# EasyBMS.net
KiCad netlist of a schematic drawn in EAGLE
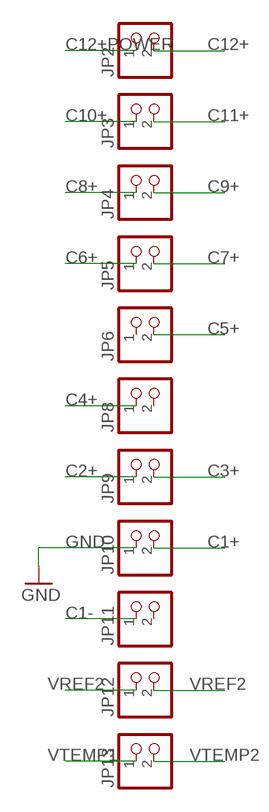
[diagram p0: schematic, sheet 1, part 1 of 3]
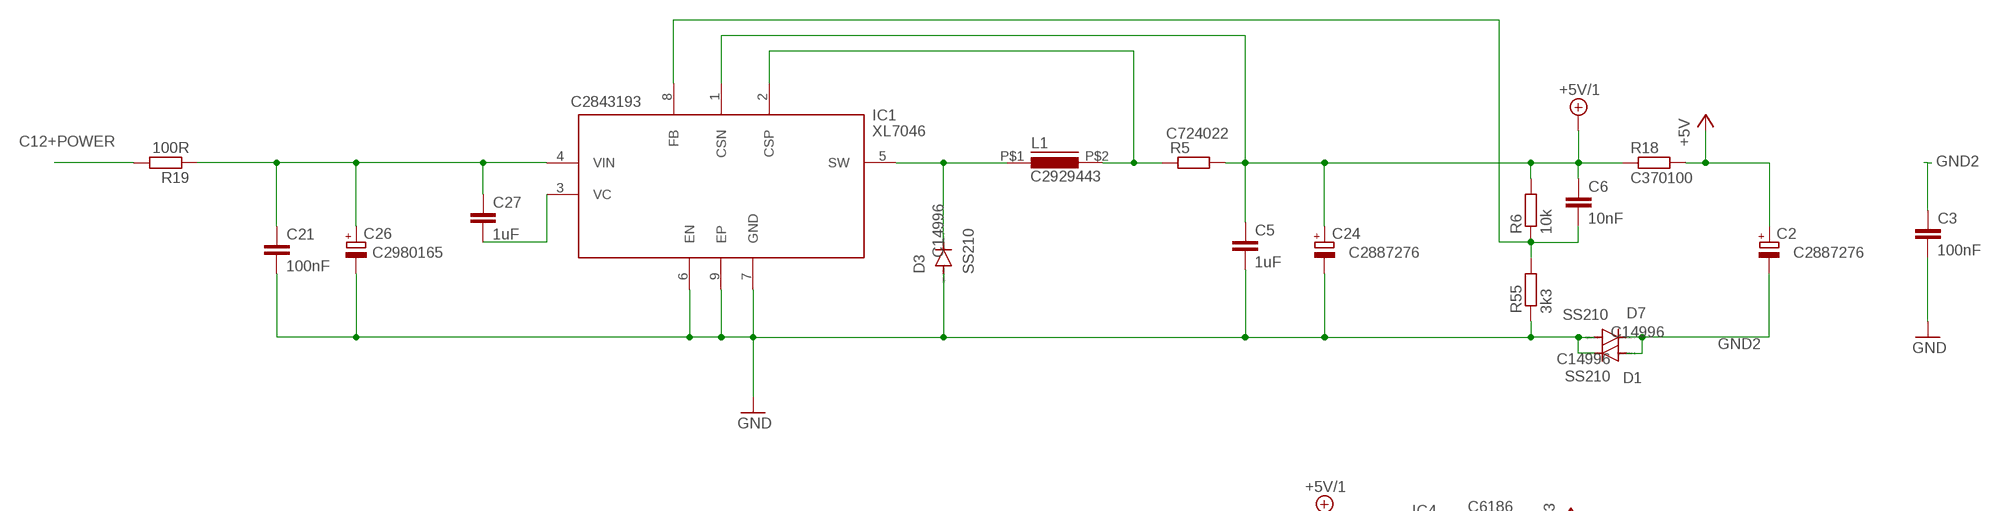
[diagram p1: schematic, sheet 1, part 2 of 3]
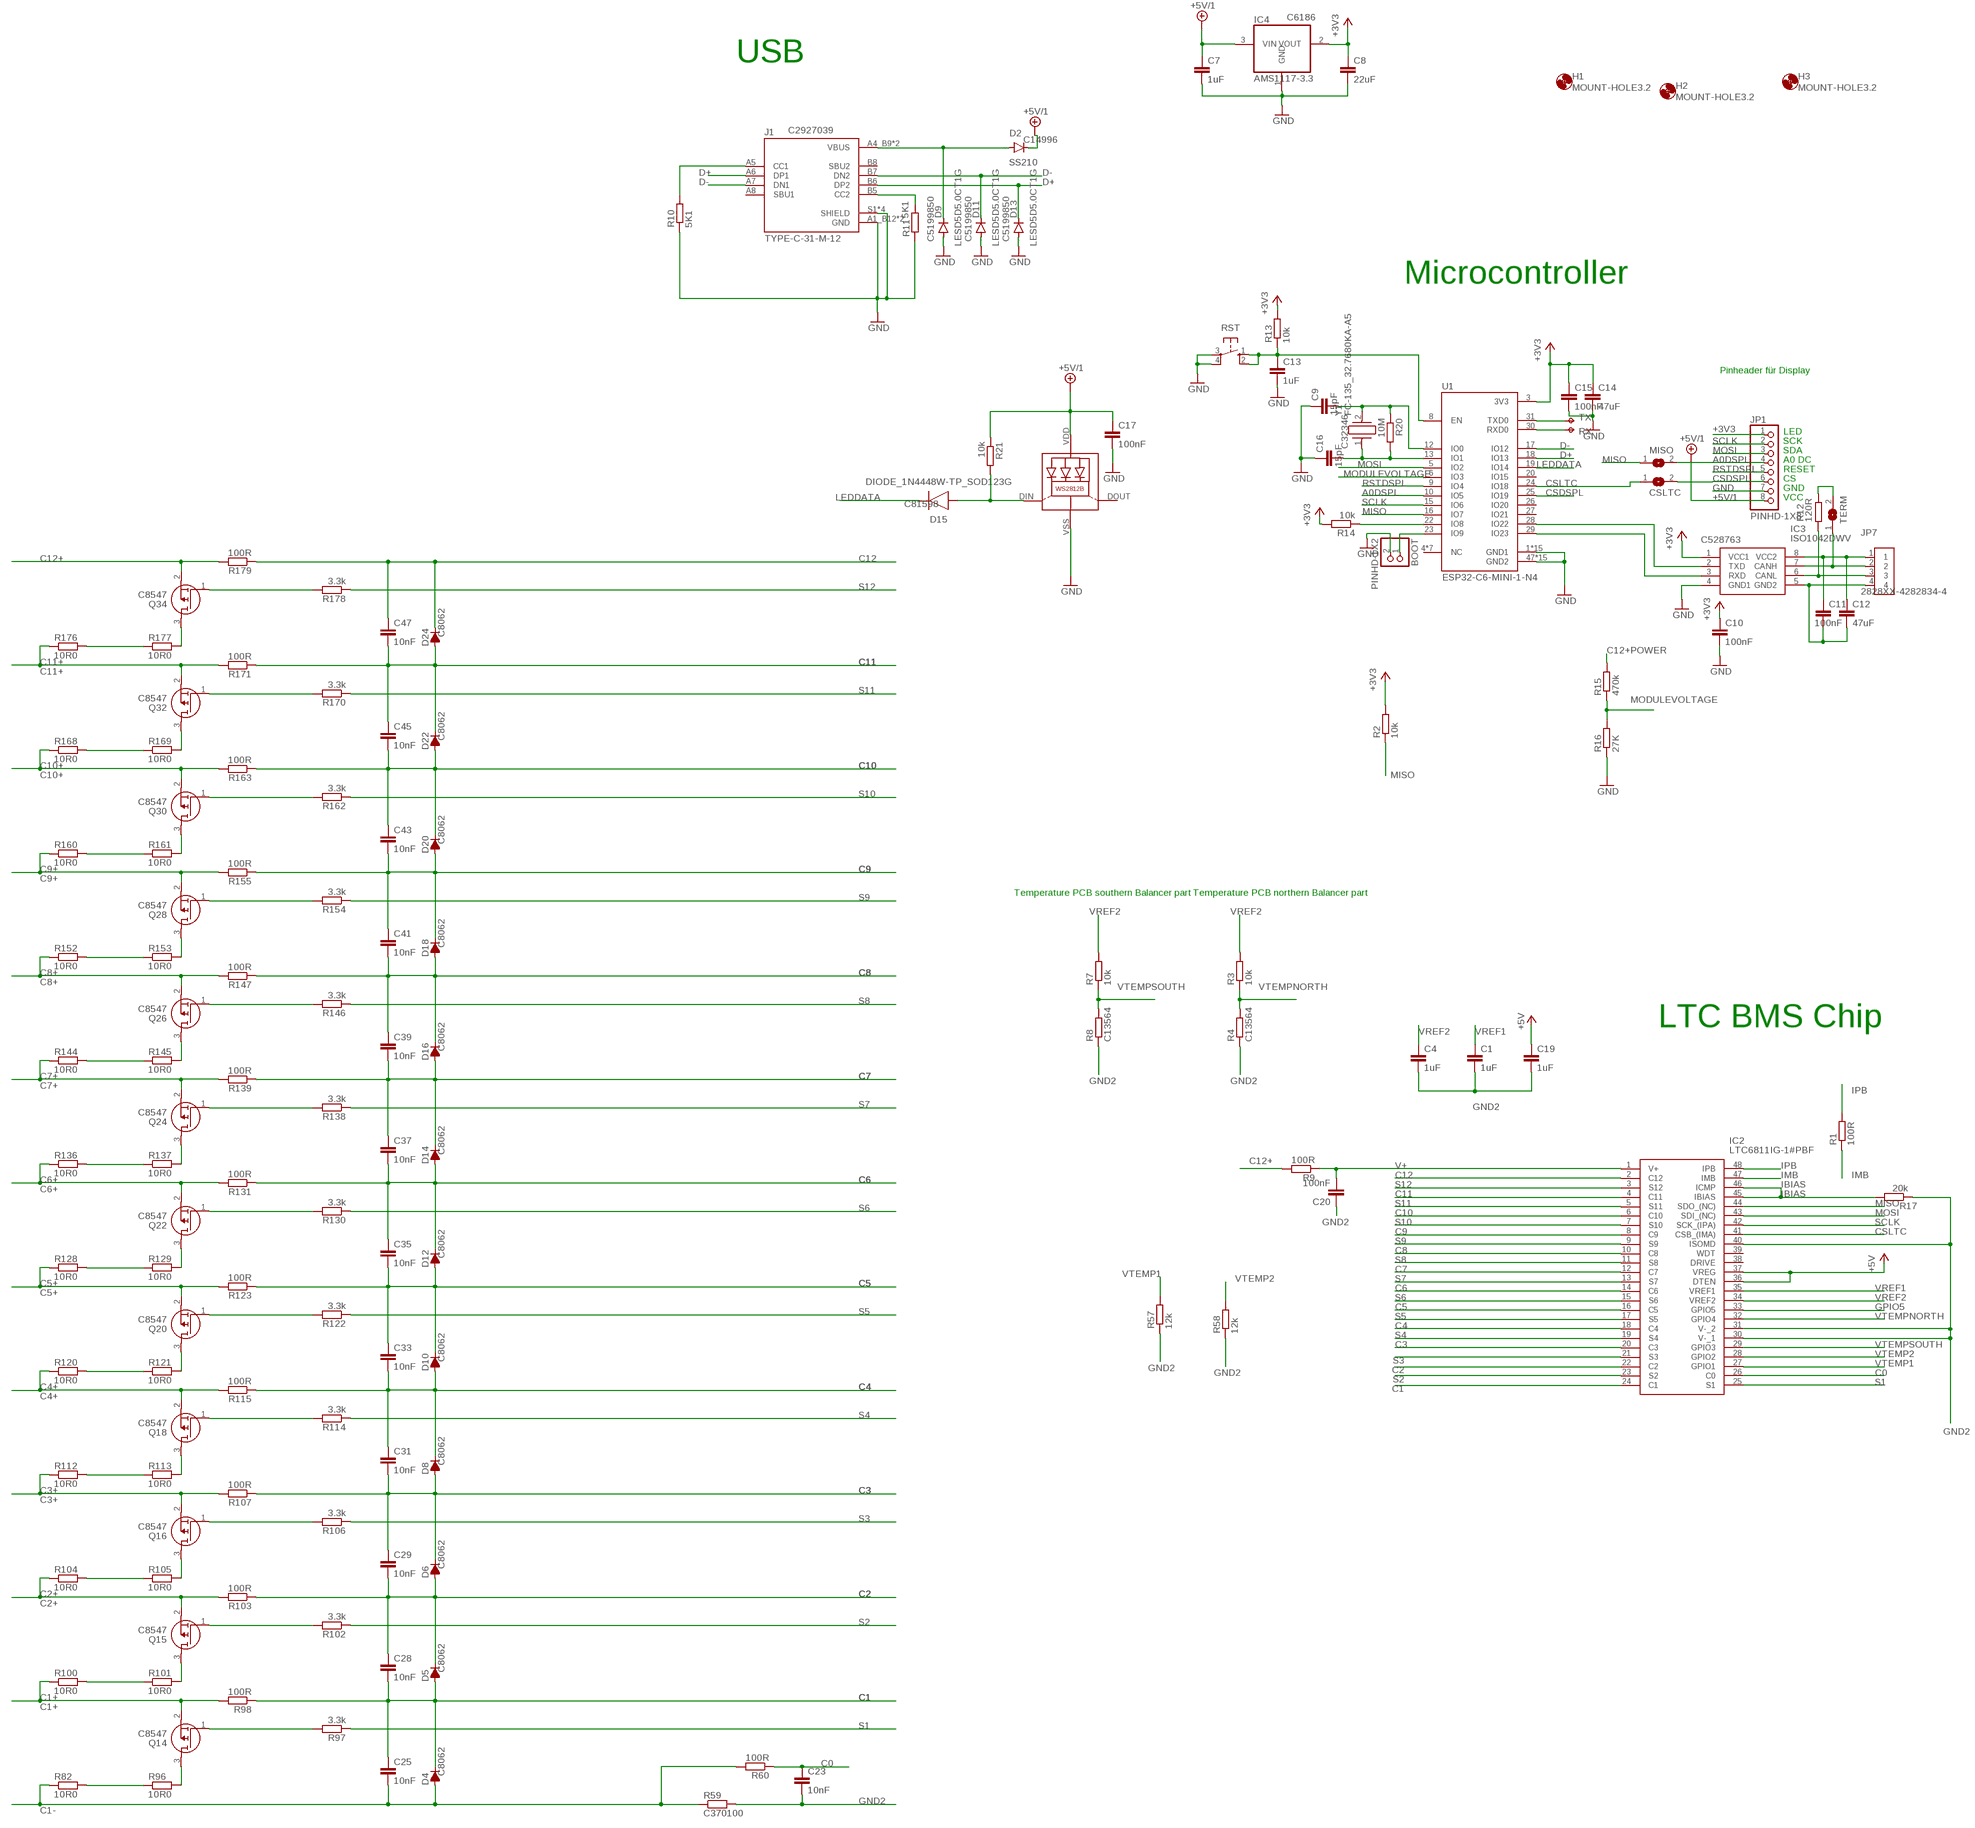
[diagram p2: schematic, sheet 1, part 3 of 3]

(export (version "E")
  (design (tool "Eeschema 10.0.6"))
  (components
    (comp (ref "BOOT")
      (value "PINHD-1X2")
      (footprint "eagle-import:1X02")
      (libsource (lib "eagle-import") (part "PINHD-1X2"))
    )
    (comp (ref "C1")
      (value "1uF")
      (footprint "eagle-import:C0402")
      (libsource (lib "eagle-import") (part "C-EUC0402"))
    )
    (comp (ref "C2")
      (value "CPOL-EU153CLV-0605")
      (footprint "eagle-import:153CLV-0605")
      (fields (field (name "LCSC") "C2887276"))
      (libsource (lib "eagle-import") (part "CPOL-EU153CLV-0605"))
    )
    (comp (ref "C3")
      (value "100nF")
      (footprint "eagle-import:C0402")
      (libsource (lib "eagle-import") (part "C-EUC0402"))
    )
    (comp (ref "C4")
      (value "1uF")
      (footprint "eagle-import:C0402")
      (libsource (lib "eagle-import") (part "C-EUC0402"))
    )
    (comp (ref "C5")
      (value "1uF")
      (footprint "eagle-import:C0402")
      (libsource (lib "eagle-import") (part "C-EUC0402"))
    )
    (comp (ref "C6")
      (value "10nF")
      (footprint "eagle-import:C0402")
      (libsource (lib "eagle-import") (part "C-EUC0402"))
    )
    (comp (ref "C7")
      (value "1uF")
      (footprint "eagle-import:C0402")
      (libsource (lib "eagle-import") (part "C-EUC0402"))
    )
    (comp (ref "C8")
      (value "22uF")
      (footprint "eagle-import:C0603")
      (libsource (lib "eagle-import") (part "C-EUC0603"))
    )
    (comp (ref "C9")
      (value "15pF")
      (footprint "eagle-import:C0402")
      (libsource (lib "eagle-import") (part "C-EUC0402"))
    )
    (comp (ref "C10")
      (value "100nF")
      (footprint "eagle-import:C0402")
      (libsource (lib "eagle-import") (part "C-EUC0402"))
    )
    (comp (ref "C11")
      (value "100nF")
      (footprint "eagle-import:C0402")
      (libsource (lib "eagle-import") (part "C-EUC0402"))
    )
    (comp (ref "C12")
      (value "47uF")
      (footprint "eagle-import:C1206")
      (libsource (lib "eagle-import") (part "C-EUC1206"))
    )
    (comp (ref "C13")
      (value "1uF")
      (footprint "eagle-import:C0402")
      (libsource (lib "eagle-import") (part "C-EUC0402"))
    )
    (comp (ref "C14")
      (value "47uF")
      (footprint "eagle-import:C0805")
      (libsource (lib "eagle-import") (part "C-EUC0805"))
    )
    (comp (ref "C15")
      (value "100nF")
      (footprint "eagle-import:C0402")
      (libsource (lib "eagle-import") (part "C-EUC0402"))
    )
    (comp (ref "C16")
      (value "15pF")
      (footprint "eagle-import:C0402")
      (libsource (lib "eagle-import") (part "C-EUC0402"))
    )
    (comp (ref "C17")
      (value "100nF")
      (footprint "eagle-import:C0402")
      (libsource (lib "eagle-import") (part "C-EUC0402"))
    )
    (comp (ref "C19")
      (value "1uF")
      (footprint "eagle-import:C0402")
      (libsource (lib "eagle-import") (part "C-EUC0402"))
    )
    (comp (ref "C20")
      (value "100nF")
      (footprint "eagle-import:C0805")
      (libsource (lib "eagle-import") (part "C-EUC0805"))
    )
    (comp (ref "C21")
      (value "100nF")
      (footprint "eagle-import:C0805")
      (libsource (lib "eagle-import") (part "C-EUC0805"))
    )
    (comp (ref "C23")
      (value "10nF")
      (footprint "eagle-import:C0402")
      (libsource (lib "eagle-import") (part "C-EUC0402"))
    )
    (comp (ref "C24")
      (value "CPOL-EU153CLV-0605")
      (footprint "eagle-import:153CLV-0605")
      (fields (field (name "LCSC") "C2887276"))
      (libsource (lib "eagle-import") (part "CPOL-EU153CLV-0605"))
    )
    (comp (ref "C25")
      (value "10nF")
      (footprint "eagle-import:C0402")
      (libsource (lib "eagle-import") (part "C-EUC0402"))
    )
    (comp (ref "C26")
      (value "CPOL-EU153CLV-0605")
      (footprint "eagle-import:153CLV-0605")
      (fields (field (name "LCSC") "C2980165"))
      (libsource (lib "eagle-import") (part "CPOL-EU153CLV-0605"))
    )
    (comp (ref "C27")
      (value "1uF")
      (footprint "eagle-import:C0603")
      (libsource (lib "eagle-import") (part "C-EUC0603"))
    )
    (comp (ref "C28")
      (value "10nF")
      (footprint "eagle-import:C0402")
      (libsource (lib "eagle-import") (part "C-EUC0402"))
    )
    (comp (ref "C29")
      (value "10nF")
      (footprint "eagle-import:C0402")
      (libsource (lib "eagle-import") (part "C-EUC0402"))
    )
    (comp (ref "C31")
      (value "10nF")
      (footprint "eagle-import:C0402")
      (libsource (lib "eagle-import") (part "C-EUC0402"))
    )
    (comp (ref "C33")
      (value "10nF")
      (footprint "eagle-import:C0402")
      (libsource (lib "eagle-import") (part "C-EUC0402"))
    )
    (comp (ref "C35")
      (value "10nF")
      (footprint "eagle-import:C0402")
      (libsource (lib "eagle-import") (part "C-EUC0402"))
    )
    (comp (ref "C37")
      (value "10nF")
      (footprint "eagle-import:C0402")
      (libsource (lib "eagle-import") (part "C-EUC0402"))
    )
    (comp (ref "C39")
      (value "10nF")
      (footprint "eagle-import:C0402")
      (libsource (lib "eagle-import") (part "C-EUC0402"))
    )
    (comp (ref "C41")
      (value "10nF")
      (footprint "eagle-import:C0402")
      (libsource (lib "eagle-import") (part "C-EUC0402"))
    )
    (comp (ref "C43")
      (value "10nF")
      (footprint "eagle-import:C0402")
      (libsource (lib "eagle-import") (part "C-EUC0402"))
    )
    (comp (ref "C45")
      (value "10nF")
      (footprint "eagle-import:C0402")
      (libsource (lib "eagle-import") (part "C-EUC0402"))
    )
    (comp (ref "C47")
      (value "10nF")
      (footprint "eagle-import:C0402")
      (libsource (lib "eagle-import") (part "C-EUC0402"))
    )
    (comp (ref "CSLTC")
      (value "SJ")
      (footprint "eagle-import:SJ")
      (libsource (lib "eagle-import") (part "SJ"))
    )
    (comp (ref "D1")
      (value "SS210")
      (footprint "eagle-import:DO214AC")
      (fields (field (name "LCSC") "C14996"))
      (libsource (lib "eagle-import") (part "DIODE-DO214AC"))
    )
    (comp (ref "D2")
      (value "SS210")
      (footprint "eagle-import:DO214AC")
      (fields (field (name "LCSC") "C14996"))
      (libsource (lib "eagle-import") (part "DIODE-DO214AC"))
    )
    (comp (ref "D3")
      (value "SS210")
      (footprint "eagle-import:DO214AC")
      (fields (field (name "LCSC") "C14996"))
      (libsource (lib "eagle-import") (part "DIODE-DO214AC"))
    )
    (comp (ref "D4")
      (value "D-FILL-MLL-34")
      (footprint "eagle-import:MELF-MLL34")
      (fields (field (name "LCSC") "C8062"))
      (libsource (lib "eagle-import") (part "D-FILL-MLL-34"))
    )
    (comp (ref "D5")
      (value "D-FILL-MLL-34")
      (footprint "eagle-import:MELF-MLL34")
      (fields (field (name "LCSC") "C8062"))
      (libsource (lib "eagle-import") (part "D-FILL-MLL-34"))
    )
    (comp (ref "D6")
      (value "D-FILL-MLL-34")
      (footprint "eagle-import:MELF-MLL34")
      (fields (field (name "LCSC") "C8062"))
      (libsource (lib "eagle-import") (part "D-FILL-MLL-34"))
    )
    (comp (ref "D7")
      (value "SS210")
      (footprint "eagle-import:DO214AC")
      (fields (field (name "LCSC") "C14996"))
      (libsource (lib "eagle-import") (part "DIODE-DO214AC"))
    )
    (comp (ref "D8")
      (value "D-FILL-MLL-34")
      (footprint "eagle-import:MELF-MLL34")
      (fields (field (name "LCSC") "C8062"))
      (libsource (lib "eagle-import") (part "D-FILL-MLL-34"))
    )
    (comp (ref "D9")
      (value "LESD5D5.0CT1G")
      (footprint "eagle-import:SOD523")
      (fields (field (name "LCSC") "C5199850"))
      (libsource (lib "eagle-import") (part "DIODE-SOD523"))
    )
    (comp (ref "D10")
      (value "D-FILL-MLL-34")
      (footprint "eagle-import:MELF-MLL34")
      (fields (field (name "LCSC") "C8062"))
      (libsource (lib "eagle-import") (part "D-FILL-MLL-34"))
    )
    (comp (ref "D11")
      (value "LESD5D5.0CT1G")
      (footprint "eagle-import:SOD523")
      (fields (field (name "LCSC") "C5199850"))
      (libsource (lib "eagle-import") (part "DIODE-SOD523"))
    )
    (comp (ref "D12")
      (value "D-FILL-MLL-34")
      (footprint "eagle-import:MELF-MLL34")
      (fields (field (name "LCSC") "C8062"))
      (libsource (lib "eagle-import") (part "D-FILL-MLL-34"))
    )
    (comp (ref "D13")
      (value "LESD5D5.0CT1G")
      (footprint "eagle-import:SOD523")
      (fields (field (name "LCSC") "C5199850"))
      (libsource (lib "eagle-import") (part "DIODE-SOD523"))
    )
    (comp (ref "D14")
      (value "D-FILL-MLL-34")
      (footprint "eagle-import:MELF-MLL34")
      (fields (field (name "LCSC") "C8062"))
      (libsource (lib "eagle-import") (part "D-FILL-MLL-34"))
    )
    (comp (ref "D15")
      (value "DIODE_1N4448W-TP_SOD123G")
      (footprint "eagle-import:SOD3715X135")
      (fields
        (field (name "MANUFACTURER") "Micro Commercial Co")
        (field (name "MPN") "1N4448W-TP")
        (field (name "LCSC") "C81598")
      )
      (libsource (lib "eagle-import") (part "DIODE__SOD123G1N4448W-TP"))
    )
    (comp (ref "D16")
      (value "D-FILL-MLL-34")
      (footprint "eagle-import:MELF-MLL34")
      (fields (field (name "LCSC") "C8062"))
      (libsource (lib "eagle-import") (part "D-FILL-MLL-34"))
    )
    (comp (ref "D18")
      (value "D-FILL-MLL-34")
      (footprint "eagle-import:MELF-MLL34")
      (fields (field (name "LCSC") "C8062"))
      (libsource (lib "eagle-import") (part "D-FILL-MLL-34"))
    )
    (comp (ref "D20")
      (value "D-FILL-MLL-34")
      (footprint "eagle-import:MELF-MLL34")
      (fields (field (name "LCSC") "C8062"))
      (libsource (lib "eagle-import") (part "D-FILL-MLL-34"))
    )
    (comp (ref "D22")
      (value "D-FILL-MLL-34")
      (footprint "eagle-import:MELF-MLL34")
      (fields (field (name "LCSC") "C8062"))
      (libsource (lib "eagle-import") (part "D-FILL-MLL-34"))
    )
    (comp (ref "D24")
      (value "D-FILL-MLL-34")
      (footprint "eagle-import:MELF-MLL34")
      (fields (field (name "LCSC") "C8062"))
      (libsource (lib "eagle-import") (part "D-FILL-MLL-34"))
    )
    (comp (ref "H1")
      (value "MOUNT-HOLE3.2")
      (footprint "eagle-import:3,2")
      (libsource (lib "eagle-import") (part "MOUNT-HOLE3.2"))
    )
    (comp (ref "H2")
      (value "MOUNT-HOLE3.2")
      (footprint "eagle-import:3,2")
      (libsource (lib "eagle-import") (part "MOUNT-HOLE3.2"))
    )
    (comp (ref "H3")
      (value "MOUNT-HOLE3.2")
      (footprint "eagle-import:3,2")
      (libsource (lib "eagle-import") (part "MOUNT-HOLE3.2"))
    )
    (comp (ref "IC1")
      (value "XL7046")
      (footprint "eagle-import:SOIC127P600X170-9N")
      (fields
        (field (name "MANUFACTURER_PART_NUMBER") "DRV103H")
        (field (name "MOUSER_PART_NUMBER") "595-DRV103H")
        (field (name "LCSC") "C2843193")
      )
      (libsource (lib "eagle-import") (part "XL7046"))
    )
    (comp (ref "IC2")
      (value "LTC6811IG-1#PBF")
      (footprint "eagle-import:SOP50P780X200-48N")
      (fields (field (name "MOUSER_PART_NUMBER") "584-LTC6811IG-1#PBF"))
      (libsource (lib "eagle-import") (part "LTC6811IG-1#PBF"))
    )
    (comp (ref "IC3")
      (value "ISO1042DWV")
      (footprint "eagle-import:SOIC127P1150X280-8N")
      (fields (field (name "MOUSER_PART_NUMBER") "595-ISO1042DWV") (field (name "LCSC") "C528763"))
      (libsource (lib "eagle-import") (part "ISO1042DWV"))
    )
    (comp (ref "IC4")
      (value "AMS1117-3.3")
      (footprint "eagle-import:SOT223")
      (fields (field (name "MPN") "REG1117") (field (name "LCSC") "C6186"))
      (libsource (lib "eagle-import") (part "REG1117"))
    )
    (comp (ref "J1")
      (value "TYPE-C-31-M-12")
      (footprint "eagle-import:HRO_TYPE-C-31-M-12")
      (fields (field (name "MF") "HRO Electronics Co., Ltd.") (field (name "LCSC") "C2927039"))
      (libsource (lib "eagle-import") (part "TYPE-C-31-M-12"))
    )
    (comp (ref "JP1")
      (value "PINHD-1X8")
      (footprint "eagle-import:1X08")
      (libsource (lib "eagle-import") (part "PINHD-1X8"))
    )
    (comp (ref "JP2")
      (value "PINHD-1X2")
      (footprint "eagle-import:1X02")
      (libsource (lib "eagle-import") (part "pinhead_own_PINHD-1X2"))
    )
    (comp (ref "JP3")
      (value "PINHD-1X2")
      (footprint "eagle-import:1X02")
      (libsource (lib "eagle-import") (part "pinhead_own_PINHD-1X2"))
    )
    (comp (ref "JP4")
      (value "PINHD-1X2")
      (footprint "eagle-import:1X02")
      (libsource (lib "eagle-import") (part "pinhead_own_PINHD-1X2"))
    )
    (comp (ref "JP5")
      (value "PINHD-1X2")
      (footprint "eagle-import:1X02")
      (libsource (lib "eagle-import") (part "pinhead_own_PINHD-1X2"))
    )
    (comp (ref "JP6")
      (value "PINHD-1X2")
      (footprint "eagle-import:1X02")
      (libsource (lib "eagle-import") (part "pinhead_own_PINHD-1X2"))
    )
    (comp (ref "JP7")
      (value "2828XX-4282834-4")
      (footprint "eagle-import:TERMBLK_254-4N")
      (fields (field (name "MANUFACTURER") "TE Connectivity AMP Connectors") (field (name "MPN") "282834-4"))
      (libsource (lib "eagle-import") (part "2828XX-4282834-4"))
    )
    (comp (ref "JP8")
      (value "PINHD-1X2")
      (footprint "eagle-import:1X02")
      (libsource (lib "eagle-import") (part "pinhead_own_PINHD-1X2"))
    )
    (comp (ref "JP9")
      (value "PINHD-1X2")
      (footprint "eagle-import:1X02")
      (libsource (lib "eagle-import") (part "pinhead_own_PINHD-1X2"))
    )
    (comp (ref "JP10")
      (value "PINHD-1X2")
      (footprint "eagle-import:1X02")
      (libsource (lib "eagle-import") (part "pinhead_own_PINHD-1X2"))
    )
    (comp (ref "JP11")
      (value "PINHD-1X2")
      (footprint "eagle-import:1X02")
      (libsource (lib "eagle-import") (part "pinhead_own_PINHD-1X2"))
    )
    (comp (ref "JP12")
      (value "PINHD-1X2")
      (footprint "eagle-import:1X02")
      (libsource (lib "eagle-import") (part "pinhead_own_PINHD-1X2"))
    )
    (comp (ref "JP13")
      (value "PINHD-1X2")
      (footprint "eagle-import:1X02")
      (libsource (lib "eagle-import") (part "pinhead_own_PINHD-1X2"))
    )
    (comp (ref "L1")
      (value "C2929443")
      (footprint "eagle-import:CY75-100UH")
      (libsource (lib "eagle-import") (part "CY75-100UH"))
    )
    (comp (ref "LED2")
      (value "XL-1615RGBC-WS2812B")
      (footprint "eagle-import:XL-1615RGBC-WS2812B")
      (libsource (lib "eagle-import") (part "XL-1615RGBC-WS2812B"))
    )
    (comp (ref "MISO")
      (value "SJ")
      (footprint "eagle-import:SJ")
      (libsource (lib "eagle-import") (part "SJ"))
    )
    (comp (ref "Q14")
      (value "C8547")
      (footprint "eagle-import:PG-SOT-23")
      (fields
        (field (name "MANUFACTURER_PART_NUMBER") "BSS308PEH6327XTSA1")
        (field (name "MOUSER_PART_NUMBER") "726-BSS308PEH6327XTS")
      )
      (libsource (lib "eagle-import") (part "BSS308PEH6327XTSA1"))
    )
    (comp (ref "Q15")
      (value "C8547")
      (footprint "eagle-import:PG-SOT-23")
      (fields
        (field (name "MANUFACTURER_PART_NUMBER") "BSS308PEH6327XTSA1")
        (field (name "MOUSER_PART_NUMBER") "726-BSS308PEH6327XTS")
      )
      (libsource (lib "eagle-import") (part "BSS308PEH6327XTSA1"))
    )
    (comp (ref "Q16")
      (value "C8547")
      (footprint "eagle-import:PG-SOT-23")
      (fields
        (field (name "MANUFACTURER_PART_NUMBER") "BSS308PEH6327XTSA1")
        (field (name "MOUSER_PART_NUMBER") "726-BSS308PEH6327XTS")
      )
      (libsource (lib "eagle-import") (part "BSS308PEH6327XTSA1"))
    )
    (comp (ref "Q18")
      (value "C8547")
      (footprint "eagle-import:PG-SOT-23")
      (fields
        (field (name "MANUFACTURER_PART_NUMBER") "BSS308PEH6327XTSA1")
        (field (name "MOUSER_PART_NUMBER") "726-BSS308PEH6327XTS")
      )
      (libsource (lib "eagle-import") (part "BSS308PEH6327XTSA1"))
    )
    (comp (ref "Q20")
      (value "C8547")
      (footprint "eagle-import:PG-SOT-23")
      (fields
        (field (name "MANUFACTURER_PART_NUMBER") "BSS308PEH6327XTSA1")
        (field (name "MOUSER_PART_NUMBER") "726-BSS308PEH6327XTS")
      )
      (libsource (lib "eagle-import") (part "BSS308PEH6327XTSA1"))
    )
    (comp (ref "Q22")
      (value "C8547")
      (footprint "eagle-import:PG-SOT-23")
      (fields
        (field (name "MANUFACTURER_PART_NUMBER") "BSS308PEH6327XTSA1")
        (field (name "MOUSER_PART_NUMBER") "726-BSS308PEH6327XTS")
      )
      (libsource (lib "eagle-import") (part "BSS308PEH6327XTSA1"))
    )
    (comp (ref "Q24")
      (value "C8547")
      (footprint "eagle-import:PG-SOT-23")
      (fields
        (field (name "MANUFACTURER_PART_NUMBER") "BSS308PEH6327XTSA1")
        (field (name "MOUSER_PART_NUMBER") "726-BSS308PEH6327XTS")
      )
      (libsource (lib "eagle-import") (part "BSS308PEH6327XTSA1"))
    )
    (comp (ref "Q26")
      (value "C8547")
      (footprint "eagle-import:PG-SOT-23")
      (fields
        (field (name "MANUFACTURER_PART_NUMBER") "BSS308PEH6327XTSA1")
        (field (name "MOUSER_PART_NUMBER") "726-BSS308PEH6327XTS")
      )
      (libsource (lib "eagle-import") (part "BSS308PEH6327XTSA1"))
    )
    (comp (ref "Q28")
      (value "C8547")
      (footprint "eagle-import:PG-SOT-23")
      (fields
        (field (name "MANUFACTURER_PART_NUMBER") "BSS308PEH6327XTSA1")
        (field (name "MOUSER_PART_NUMBER") "726-BSS308PEH6327XTS")
      )
      (libsource (lib "eagle-import") (part "BSS308PEH6327XTSA1"))
    )
    (comp (ref "Q30")
      (value "C8547")
      (footprint "eagle-import:PG-SOT-23")
      (fields
        (field (name "MANUFACTURER_PART_NUMBER") "BSS308PEH6327XTSA1")
        (field (name "MOUSER_PART_NUMBER") "726-BSS308PEH6327XTS")
      )
      (libsource (lib "eagle-import") (part "BSS308PEH6327XTSA1"))
    )
    (comp (ref "Q32")
      (value "C8547")
      (footprint "eagle-import:PG-SOT-23")
      (fields
        (field (name "MANUFACTURER_PART_NUMBER") "BSS308PEH6327XTSA1")
        (field (name "MOUSER_PART_NUMBER") "726-BSS308PEH6327XTS")
      )
      (libsource (lib "eagle-import") (part "BSS308PEH6327XTSA1"))
    )
    (comp (ref "Q34")
      (value "C8547")
      (footprint "eagle-import:PG-SOT-23")
      (fields
        (field (name "MANUFACTURER_PART_NUMBER") "BSS308PEH6327XTSA1")
        (field (name "MOUSER_PART_NUMBER") "726-BSS308PEH6327XTS")
      )
      (libsource (lib "eagle-import") (part "BSS308PEH6327XTSA1"))
    )
    (comp (ref "R1")
      (value "100R")
      (footprint "eagle-import:R0603")
      (libsource (lib "eagle-import") (part "R-EU_R0603"))
    )
    (comp (ref "R2")
      (value "10k")
      (footprint "eagle-import:R0402")
      (libsource (lib "eagle-import") (part "R-EU_R0402"))
    )
    (comp (ref "R3")
      (value "10k")
      (footprint "eagle-import:R0603")
      (libsource (lib "eagle-import") (part "R-EU_R0603"))
    )
    (comp (ref "R4")
      (value "C13564")
      (footprint "eagle-import:R0603")
      (libsource (lib "eagle-import") (part "R-EU_R0603"))
    )
    (comp (ref "R5")
      (value "R-EU_R0402")
      (footprint "eagle-import:R0402")
      (fields (field (name "LCSC") "C724022"))
      (libsource (lib "eagle-import") (part "R-EU_R0402"))
    )
    (comp (ref "R6")
      (value "10k")
      (footprint "eagle-import:R0402")
      (libsource (lib "eagle-import") (part "R-EU_R0402"))
    )
    (comp (ref "R7")
      (value "10k")
      (footprint "eagle-import:R0603")
      (libsource (lib "eagle-import") (part "R-EU_R0603"))
    )
    (comp (ref "R8")
      (value "C13564")
      (footprint "eagle-import:R0603")
      (libsource (lib "eagle-import") (part "R-EU_R0603"))
    )
    (comp (ref "R9")
      (value "100R")
      (footprint "eagle-import:R0402")
      (libsource (lib "eagle-import") (part "R-EU_R0402"))
    )
    (comp (ref "R10")
      (value "5K1")
      (footprint "eagle-import:R0402")
      (libsource (lib "eagle-import") (part "R-EU_R0402"))
    )
    (comp (ref "R11")
      (value "5K1")
      (footprint "eagle-import:R0402")
      (libsource (lib "eagle-import") (part "R-EU_R0402"))
    )
    (comp (ref "R12")
      (value "120R")
      (footprint "eagle-import:R0402")
      (libsource (lib "eagle-import") (part "R-EU_R0402"))
    )
    (comp (ref "R13")
      (value "10k")
      (footprint "eagle-import:R0402")
      (libsource (lib "eagle-import") (part "R-EU_R0402"))
    )
    (comp (ref "R14")
      (value "10k")
      (footprint "eagle-import:R0402")
      (libsource (lib "eagle-import") (part "R-EU_R0402"))
    )
    (comp (ref "R15")
      (value "470k")
      (footprint "eagle-import:R0603")
      (libsource (lib "eagle-import") (part "R-EU_R0603"))
    )
    (comp (ref "R16")
      (value "27K")
      (footprint "eagle-import:R0603")
      (libsource (lib "eagle-import") (part "R-EU_R0603"))
    )
    (comp (ref "R17")
      (value "20k")
      (footprint "eagle-import:R0603")
      (libsource (lib "eagle-import") (part "R-EU_R0603"))
    )
    (comp (ref "R18")
      (value "C370100")
      (footprint "eagle-import:R1206")
      (libsource (lib "eagle-import") (part "R-EU_R1206"))
    )
    (comp (ref "R19")
      (value "100R")
      (footprint "eagle-import:R1206")
      (libsource (lib "eagle-import") (part "R-EU_R1206"))
    )
    (comp (ref "R20")
      (value "10M")
      (footprint "eagle-import:R0402")
      (libsource (lib "eagle-import") (part "R-EU_R0402"))
    )
    (comp (ref "R21")
      (value "10k")
      (footprint "eagle-import:R0402")
      (libsource (lib "eagle-import") (part "R-EU_R0402"))
    )
    (comp (ref "R55")
      (value "3k3")
      (footprint "eagle-import:R0402")
      (libsource (lib "eagle-import") (part "R-EU_R0402"))
    )
    (comp (ref "R57")
      (value "12k")
      (footprint "eagle-import:R0402")
      (libsource (lib "eagle-import") (part "R-EU_R0402"))
    )
    (comp (ref "R58")
      (value "12k")
      (footprint "eagle-import:R0402")
      (libsource (lib "eagle-import") (part "R-EU_R0402"))
    )
    (comp (ref "R59")
      (value "C370100")
      (footprint "eagle-import:R1206")
      (libsource (lib "eagle-import") (part "R-EU_R1206"))
    )
    (comp (ref "R60")
      (value "100R")
      (footprint "eagle-import:R0402")
      (libsource (lib "eagle-import") (part "R-EU_R0402"))
    )
    (comp (ref "R82")
      (value "10R0")
      (footprint "eagle-import:R1206")
      (libsource (lib "eagle-import") (part "R-EU_R1206"))
    )
    (comp (ref "R96")
      (value "10R0")
      (footprint "eagle-import:R1206")
      (libsource (lib "eagle-import") (part "R-EU_R1206"))
    )
    (comp (ref "R97")
      (value "3.3k")
      (footprint "eagle-import:R0402")
      (libsource (lib "eagle-import") (part "R-EU_R0402"))
    )
    (comp (ref "R98")
      (value "100R")
      (footprint "eagle-import:R0402")
      (libsource (lib "eagle-import") (part "R-EU_R0402"))
    )
    (comp (ref "R100")
      (value "10R0")
      (footprint "eagle-import:R1206")
      (libsource (lib "eagle-import") (part "R-EU_R1206"))
    )
    (comp (ref "R101")
      (value "10R0")
      (footprint "eagle-import:R1206")
      (libsource (lib "eagle-import") (part "R-EU_R1206"))
    )
    (comp (ref "R102")
      (value "3.3k")
      (footprint "eagle-import:R0402")
      (libsource (lib "eagle-import") (part "R-EU_R0402"))
    )
    (comp (ref "R103")
      (value "100R")
      (footprint "eagle-import:R0402")
      (libsource (lib "eagle-import") (part "R-EU_R0402"))
    )
    (comp (ref "R104")
      (value "10R0")
      (footprint "eagle-import:R1206")
      (libsource (lib "eagle-import") (part "R-EU_R1206"))
    )
    (comp (ref "R105")
      (value "10R0")
      (footprint "eagle-import:R1206")
      (libsource (lib "eagle-import") (part "R-EU_R1206"))
    )
    (comp (ref "R106")
      (value "3.3k")
      (footprint "eagle-import:R0402")
      (libsource (lib "eagle-import") (part "R-EU_R0402"))
    )
    (comp (ref "R107")
      (value "100R")
      (footprint "eagle-import:R0402")
      (libsource (lib "eagle-import") (part "R-EU_R0402"))
    )
    (comp (ref "R112")
      (value "10R0")
      (footprint "eagle-import:R1206")
      (libsource (lib "eagle-import") (part "R-EU_R1206"))
    )
    (comp (ref "R113")
      (value "10R0")
      (footprint "eagle-import:R1206")
      (libsource (lib "eagle-import") (part "R-EU_R1206"))
    )
    (comp (ref "R114")
      (value "3.3k")
      (footprint "eagle-import:R0402")
      (libsource (lib "eagle-import") (part "R-EU_R0402"))
    )
    (comp (ref "R115")
      (value "100R")
      (footprint "eagle-import:R0402")
      (libsource (lib "eagle-import") (part "R-EU_R0402"))
    )
    (comp (ref "R120")
      (value "10R0")
      (footprint "eagle-import:R1206")
      (libsource (lib "eagle-import") (part "R-EU_R1206"))
    )
    (comp (ref "R121")
      (value "10R0")
      (footprint "eagle-import:R1206")
      (libsource (lib "eagle-import") (part "R-EU_R1206"))
    )
    (comp (ref "R122")
      (value "3.3k")
      (footprint "eagle-import:R0402")
      (libsource (lib "eagle-import") (part "R-EU_R0402"))
    )
    (comp (ref "R123")
      (value "100R")
      (footprint "eagle-import:R0402")
      (libsource (lib "eagle-import") (part "R-EU_R0402"))
    )
    (comp (ref "R128")
      (value "10R0")
      (footprint "eagle-import:R1206")
      (libsource (lib "eagle-import") (part "R-EU_R1206"))
    )
    (comp (ref "R129")
      (value "10R0")
      (footprint "eagle-import:R1206")
      (libsource (lib "eagle-import") (part "R-EU_R1206"))
    )
    (comp (ref "R130")
      (value "3.3k")
      (footprint "eagle-import:R0402")
      (libsource (lib "eagle-import") (part "R-EU_R0402"))
    )
    (comp (ref "R131")
      (value "100R")
      (footprint "eagle-import:R0402")
      (libsource (lib "eagle-import") (part "R-EU_R0402"))
    )
    (comp (ref "R136")
      (value "10R0")
      (footprint "eagle-import:R1206")
      (libsource (lib "eagle-import") (part "R-EU_R1206"))
    )
    (comp (ref "R137")
      (value "10R0")
      (footprint "eagle-import:R1206")
      (libsource (lib "eagle-import") (part "R-EU_R1206"))
    )
    (comp (ref "R138")
      (value "3.3k")
      (footprint "eagle-import:R0402")
      (libsource (lib "eagle-import") (part "R-EU_R0402"))
    )
    (comp (ref "R139")
      (value "100R")
      (footprint "eagle-import:R0402")
      (libsource (lib "eagle-import") (part "R-EU_R0402"))
    )
    (comp (ref "R144")
      (value "10R0")
      (footprint "eagle-import:R1206")
      (libsource (lib "eagle-import") (part "R-EU_R1206"))
    )
    (comp (ref "R145")
      (value "10R0")
      (footprint "eagle-import:R1206")
      (libsource (lib "eagle-import") (part "R-EU_R1206"))
    )
    (comp (ref "R146")
      (value "3.3k")
      (footprint "eagle-import:R0402")
      (libsource (lib "eagle-import") (part "R-EU_R0402"))
    )
    (comp (ref "R147")
      (value "100R")
      (footprint "eagle-import:R0402")
      (libsource (lib "eagle-import") (part "R-EU_R0402"))
    )
    (comp (ref "R152")
      (value "10R0")
      (footprint "eagle-import:R1206")
      (libsource (lib "eagle-import") (part "R-EU_R1206"))
    )
    (comp (ref "R153")
      (value "10R0")
      (footprint "eagle-import:R1206")
      (libsource (lib "eagle-import") (part "R-EU_R1206"))
    )
    (comp (ref "R154")
      (value "3.3k")
      (footprint "eagle-import:R0402")
      (libsource (lib "eagle-import") (part "R-EU_R0402"))
    )
    (comp (ref "R155")
      (value "100R")
      (footprint "eagle-import:R0402")
      (libsource (lib "eagle-import") (part "R-EU_R0402"))
    )
    (comp (ref "R160")
      (value "10R0")
      (footprint "eagle-import:R1206")
      (libsource (lib "eagle-import") (part "R-EU_R1206"))
    )
    (comp (ref "R161")
      (value "10R0")
      (footprint "eagle-import:R1206")
      (libsource (lib "eagle-import") (part "R-EU_R1206"))
    )
    (comp (ref "R162")
      (value "3.3k")
      (footprint "eagle-import:R0402")
      (libsource (lib "eagle-import") (part "R-EU_R0402"))
    )
    (comp (ref "R163")
      (value "100R")
      (footprint "eagle-import:R0402")
      (libsource (lib "eagle-import") (part "R-EU_R0402"))
    )
    (comp (ref "R168")
      (value "10R0")
      (footprint "eagle-import:R1206")
      (libsource (lib "eagle-import") (part "R-EU_R1206"))
    )
    (comp (ref "R169")
      (value "10R0")
      (footprint "eagle-import:R1206")
      (libsource (lib "eagle-import") (part "R-EU_R1206"))
    )
    (comp (ref "R170")
      (value "3.3k")
      (footprint "eagle-import:R0402")
      (libsource (lib "eagle-import") (part "R-EU_R0402"))
    )
    (comp (ref "R171")
      (value "100R")
      (footprint "eagle-import:R0402")
      (libsource (lib "eagle-import") (part "R-EU_R0402"))
    )
    (comp (ref "R176")
      (value "10R0")
      (footprint "eagle-import:R1206")
      (libsource (lib "eagle-import") (part "R-EU_R1206"))
    )
    (comp (ref "R177")
      (value "10R0")
      (footprint "eagle-import:R1206")
      (libsource (lib "eagle-import") (part "R-EU_R1206"))
    )
    (comp (ref "R178")
      (value "3.3k")
      (footprint "eagle-import:R0402")
      (libsource (lib "eagle-import") (part "R-EU_R0402"))
    )
    (comp (ref "R179")
      (value "100R")
      (footprint "eagle-import:R0402")
      (libsource (lib "eagle-import") (part "R-EU_R0402"))
    )
    (comp (ref "RST")
      (value "10-XX")
      (footprint "eagle-import:B3F-10XX")
      (fields (field (name "MPN") "B3F-1000"))
      (libsource (lib "eagle-import") (part "10-XX"))
    )
    (comp (ref "RX")
      (value "TPB2,54")
      (footprint "eagle-import:B2,54")
      (libsource (lib "eagle-import") (part "TPB2,54"))
    )
    (comp (ref "TERM")
      (value "SJ")
      (footprint "eagle-import:SJ")
      (libsource (lib "eagle-import") (part "SJ"))
    )
    (comp (ref "TX")
      (value "TPB2,54")
      (footprint "eagle-import:B2,54")
      (libsource (lib "eagle-import") (part "TPB2,54"))
    )
    (comp (ref "U1")
      (value "ESP32-C6-MINI-1-N4")
      (footprint "eagle-import:XCVR_ESP32-C6-MINI-1-N4")
      (fields (field (name "MANUFACTURER") "Espressif Systems"))
      (libsource (lib "eagle-import") (part "ESP32-C6-MINI-1-N4"))
    )
    (comp (ref "Y1")
      (value "FC-135_32.7680KA-A5")
      (footprint "eagle-import:FC135327680KAA5")
      (fields
        (field (name "MANUFACTURER_PART_NUMBER") "FC-135 32.7680KA-A5")
        (field (name "MOUSER_PART_NUMBER") "732-532.7680KA-A5")
        (field (name "LCSC") "C32346")
      )
      (libsource (lib "eagle-import") (part "FC-135_32.7680KA-A5"))
    )
  )
  (nets
    (net (code "1") (name "+3V3") (class "Default")
      (node (ref "C10") (pin "1") (pinfunction "1_1") (pintype "passive"))
      (node (ref "C14") (pin "1") (pinfunction "1_1") (pintype "passive"))
      (node (ref "C15") (pin "1") (pinfunction "1_1") (pintype "passive"))
      (node (ref "C8") (pin "1") (pinfunction "1_1") (pintype "passive"))
      (node (ref "IC3") (pin "1") (pinfunction "VCC1_1") (pintype "bidirectional"))
      (node (ref "IC4") (pin "2") (pinfunction "VOUT_2") (pintype "output"))
      (node (ref "JP1") (pin "1") (pinfunction "1_1") (pintype "passive"))
      (node (ref "R13") (pin "2") (pinfunction "2_2") (pintype "passive"))
      (node (ref "R14") (pin "2") (pinfunction "2_2") (pintype "passive"))
      (node (ref "R2") (pin "2") (pinfunction "2_2") (pintype "passive"))
      (node (ref "U1") (pin "3") (pinfunction "3V3_3") (pintype "power_in"))
    )
    (net (code "2") (name "+5V") (class "Default")
      (node (ref "C19") (pin "1") (pinfunction "1_1") (pintype "passive"))
      (node (ref "C2") (pin "+") (pinfunction "+_+") (pintype "passive"))
      (node (ref "IC2") (pin "36") (pinfunction "DTEN_36") (pintype "bidirectional"))
      (node (ref "IC2") (pin "37") (pinfunction "VREG_37") (pintype "bidirectional"))
      (node (ref "R18") (pin "2") (pinfunction "2_2") (pintype "passive"))
    )
    (net (code "3") (name "+5V{slash}1") (class "Default")
      (node (ref "C17") (pin "1") (pinfunction "1_1") (pintype "passive"))
      (node (ref "C24") (pin "+") (pinfunction "+_+") (pintype "passive"))
      (node (ref "C5") (pin "1") (pinfunction "1_1") (pintype "passive"))
      (node (ref "C6") (pin "1") (pinfunction "1_1") (pintype "passive"))
      (node (ref "C7") (pin "1") (pinfunction "1_1") (pintype "passive"))
      (node (ref "D2") (pin "C") (pinfunction "C_C") (pintype "passive"))
      (node (ref "IC1") (pin "1") (pinfunction "CSN_1") (pintype "bidirectional"))
      (node (ref "IC4") (pin "3") (pinfunction "VIN_3") (pintype "input"))
      (node (ref "JP1") (pin "8") (pinfunction "8_8") (pintype "passive"))
      (node (ref "LED2") (pin "VDD") (pinfunction "VDD_VDD") (pintype "power_in"))
      (node (ref "R18") (pin "1") (pinfunction "1_1") (pintype "passive"))
      (node (ref "R21") (pin "1") (pinfunction "1_1") (pintype "passive"))
      (node (ref "R5") (pin "2") (pinfunction "2_2") (pintype "passive"))
      (node (ref "R6") (pin "2") (pinfunction "2_2") (pintype "passive"))
    )
    (net (code "4") (name "/A0DSPL") (class "Default")
      (node (ref "JP1") (pin "4") (pinfunction "4_4") (pintype "passive"))
      (node (ref "MISO") (pin "2") (pinfunction "2_2") (pintype "passive"))
      (node (ref "U1") (pin "10") (pinfunction "IO5_10") (pintype "bidirectional"))
    )
    (net (code "5") (name "/C0") (class "Default")
      (node (ref "C23") (pin "1") (pinfunction "1_1") (pintype "passive"))
      (node (ref "IC2") (pin "26") (pinfunction "C0_26") (pintype "bidirectional"))
      (node (ref "R60") (pin "1") (pinfunction "1_1") (pintype "passive"))
    )
    (net (code "6") (name "/C1") (class "Default")
      (node (ref "C25") (pin "1") (pinfunction "1_1") (pintype "passive"))
      (node (ref "C28") (pin "2") (pinfunction "2_2") (pintype "passive"))
      (node (ref "D4") (pin "1") (pinfunction "C_1") (pintype "passive"))
      (node (ref "D5") (pin "2") (pinfunction "A_2") (pintype "passive"))
      (node (ref "IC2") (pin "24") (pinfunction "C1_24") (pintype "bidirectional"))
      (node (ref "R98") (pin "1") (pinfunction "1_1") (pintype "passive"))
    )
    (net (code "7") (name "/C1+") (class "Default")
      (node (ref "JP10") (pin "2") (pinfunction "2_2") (pintype "passive"))
      (node (ref "Q14") (pin "2") (pinfunction "S_2") (pintype "bidirectional"))
      (node (ref "R100") (pin "1") (pinfunction "1_1") (pintype "passive"))
      (node (ref "R98") (pin "2") (pinfunction "2_2") (pintype "passive"))
    )
    (net (code "8") (name "/C1-") (class "Default")
      (node (ref "C25") (pin "2") (pinfunction "2_2") (pintype "passive"))
      (node (ref "D4") (pin "2") (pinfunction "A_2") (pintype "passive"))
      (node (ref "JP11") (pin "1") (pinfunction "1_1") (pintype "passive"))
      (node (ref "R59") (pin "1") (pinfunction "1_1") (pintype "passive"))
      (node (ref "R60") (pin "2") (pinfunction "2_2") (pintype "passive"))
      (node (ref "R82") (pin "1") (pinfunction "1_1") (pintype "passive"))
    )
    (net (code "9") (name "/C2") (class "Default")
      (node (ref "C28") (pin "1") (pinfunction "1_1") (pintype "passive"))
      (node (ref "C29") (pin "2") (pinfunction "2_2") (pintype "passive"))
      (node (ref "D5") (pin "1") (pinfunction "C_1") (pintype "passive"))
      (node (ref "D6") (pin "2") (pinfunction "A_2") (pintype "passive"))
      (node (ref "IC2") (pin "22") (pinfunction "C2_22") (pintype "bidirectional"))
      (node (ref "R103") (pin "1") (pinfunction "1_1") (pintype "passive"))
    )
    (net (code "10") (name "/C2+") (class "Default")
      (node (ref "JP9") (pin "1") (pinfunction "1_1") (pintype "passive"))
      (node (ref "Q15") (pin "2") (pinfunction "S_2") (pintype "bidirectional"))
      (node (ref "R103") (pin "2") (pinfunction "2_2") (pintype "passive"))
      (node (ref "R104") (pin "1") (pinfunction "1_1") (pintype "passive"))
    )
    (net (code "11") (name "/C3") (class "Default")
      (node (ref "C29") (pin "1") (pinfunction "1_1") (pintype "passive"))
      (node (ref "C31") (pin "2") (pinfunction "2_2") (pintype "passive"))
      (node (ref "D6") (pin "1") (pinfunction "C_1") (pintype "passive"))
      (node (ref "D8") (pin "2") (pinfunction "A_2") (pintype "passive"))
      (node (ref "IC2") (pin "20") (pinfunction "C3_20") (pintype "bidirectional"))
      (node (ref "R107") (pin "1") (pinfunction "1_1") (pintype "passive"))
    )
    (net (code "12") (name "/C3+") (class "Default")
      (node (ref "JP9") (pin "2") (pinfunction "2_2") (pintype "passive"))
      (node (ref "Q16") (pin "2") (pinfunction "S_2") (pintype "bidirectional"))
      (node (ref "R107") (pin "2") (pinfunction "2_2") (pintype "passive"))
      (node (ref "R112") (pin "1") (pinfunction "1_1") (pintype "passive"))
    )
    (net (code "13") (name "/C4") (class "Default")
      (node (ref "C31") (pin "1") (pinfunction "1_1") (pintype "passive"))
      (node (ref "C33") (pin "2") (pinfunction "2_2") (pintype "passive"))
      (node (ref "D10") (pin "2") (pinfunction "A_2") (pintype "passive"))
      (node (ref "D8") (pin "1") (pinfunction "C_1") (pintype "passive"))
      (node (ref "IC2") (pin "18") (pinfunction "C4_18") (pintype "bidirectional"))
      (node (ref "R115") (pin "1") (pinfunction "1_1") (pintype "passive"))
    )
    (net (code "14") (name "/C4+") (class "Default")
      (node (ref "JP8") (pin "1") (pinfunction "1_1") (pintype "passive"))
      (node (ref "Q18") (pin "2") (pinfunction "S_2") (pintype "bidirectional"))
      (node (ref "R115") (pin "2") (pinfunction "2_2") (pintype "passive"))
      (node (ref "R120") (pin "1") (pinfunction "1_1") (pintype "passive"))
    )
    (net (code "15") (name "/C5") (class "Default")
      (node (ref "C33") (pin "1") (pinfunction "1_1") (pintype "passive"))
      (node (ref "C35") (pin "2") (pinfunction "2_2") (pintype "passive"))
      (node (ref "D10") (pin "1") (pinfunction "C_1") (pintype "passive"))
      (node (ref "D12") (pin "2") (pinfunction "A_2") (pintype "passive"))
      (node (ref "IC2") (pin "16") (pinfunction "C5_16") (pintype "bidirectional"))
      (node (ref "R123") (pin "1") (pinfunction "1_1") (pintype "passive"))
    )
    (net (code "16") (name "/C5+") (class "Default")
      (node (ref "JP6") (pin "2") (pinfunction "2_2") (pintype "passive"))
      (node (ref "Q20") (pin "2") (pinfunction "S_2") (pintype "bidirectional"))
      (node (ref "R123") (pin "2") (pinfunction "2_2") (pintype "passive"))
      (node (ref "R128") (pin "1") (pinfunction "1_1") (pintype "passive"))
    )
    (net (code "17") (name "/C6") (class "Default")
      (node (ref "C35") (pin "1") (pinfunction "1_1") (pintype "passive"))
      (node (ref "C37") (pin "2") (pinfunction "2_2") (pintype "passive"))
      (node (ref "D12") (pin "1") (pinfunction "C_1") (pintype "passive"))
      (node (ref "D14") (pin "2") (pinfunction "A_2") (pintype "passive"))
      (node (ref "IC2") (pin "14") (pinfunction "C6_14") (pintype "bidirectional"))
      (node (ref "R131") (pin "1") (pinfunction "1_1") (pintype "passive"))
    )
    (net (code "18") (name "/C6+") (class "Default")
      (node (ref "JP5") (pin "1") (pinfunction "1_1") (pintype "passive"))
      (node (ref "Q22") (pin "2") (pinfunction "S_2") (pintype "bidirectional"))
      (node (ref "R131") (pin "2") (pinfunction "2_2") (pintype "passive"))
      (node (ref "R136") (pin "1") (pinfunction "1_1") (pintype "passive"))
    )
    (net (code "19") (name "/C7") (class "Default")
      (node (ref "C37") (pin "1") (pinfunction "1_1") (pintype "passive"))
      (node (ref "C39") (pin "2") (pinfunction "2_2") (pintype "passive"))
      (node (ref "D14") (pin "1") (pinfunction "C_1") (pintype "passive"))
      (node (ref "D16") (pin "2") (pinfunction "A_2") (pintype "passive"))
      (node (ref "IC2") (pin "12") (pinfunction "C7_12") (pintype "bidirectional"))
      (node (ref "R139") (pin "1") (pinfunction "1_1") (pintype "passive"))
    )
    (net (code "20") (name "/C7+") (class "Default")
      (node (ref "JP5") (pin "2") (pinfunction "2_2") (pintype "passive"))
      (node (ref "Q24") (pin "2") (pinfunction "S_2") (pintype "bidirectional"))
      (node (ref "R139") (pin "2") (pinfunction "2_2") (pintype "passive"))
      (node (ref "R144") (pin "1") (pinfunction "1_1") (pintype "passive"))
    )
    (net (code "21") (name "/C8") (class "Default")
      (node (ref "C39") (pin "1") (pinfunction "1_1") (pintype "passive"))
      (node (ref "C41") (pin "2") (pinfunction "2_2") (pintype "passive"))
      (node (ref "D16") (pin "1") (pinfunction "C_1") (pintype "passive"))
      (node (ref "D18") (pin "2") (pinfunction "A_2") (pintype "passive"))
      (node (ref "IC2") (pin "10") (pinfunction "C8_10") (pintype "bidirectional"))
      (node (ref "R147") (pin "1") (pinfunction "1_1") (pintype "passive"))
    )
    (net (code "22") (name "/C8+") (class "Default")
      (node (ref "JP4") (pin "1") (pinfunction "1_1") (pintype "passive"))
      (node (ref "Q26") (pin "2") (pinfunction "S_2") (pintype "bidirectional"))
      (node (ref "R147") (pin "2") (pinfunction "2_2") (pintype "passive"))
      (node (ref "R152") (pin "1") (pinfunction "1_1") (pintype "passive"))
    )
    (net (code "23") (name "/C9") (class "Default")
      (node (ref "C41") (pin "1") (pinfunction "1_1") (pintype "passive"))
      (node (ref "C43") (pin "2") (pinfunction "2_2") (pintype "passive"))
      (node (ref "D18") (pin "1") (pinfunction "C_1") (pintype "passive"))
      (node (ref "D20") (pin "2") (pinfunction "A_2") (pintype "passive"))
      (node (ref "IC2") (pin "8") (pinfunction "C9_8") (pintype "bidirectional"))
      (node (ref "R155") (pin "1") (pinfunction "1_1") (pintype "passive"))
    )
    (net (code "24") (name "/C9+") (class "Default")
      (node (ref "JP4") (pin "2") (pinfunction "2_2") (pintype "passive"))
      (node (ref "Q28") (pin "2") (pinfunction "S_2") (pintype "bidirectional"))
      (node (ref "R155") (pin "2") (pinfunction "2_2") (pintype "passive"))
      (node (ref "R160") (pin "1") (pinfunction "1_1") (pintype "passive"))
    )
    (net (code "25") (name "/C10") (class "Default")
      (node (ref "C43") (pin "1") (pinfunction "1_1") (pintype "passive"))
      (node (ref "C45") (pin "2") (pinfunction "2_2") (pintype "passive"))
      (node (ref "D20") (pin "1") (pinfunction "C_1") (pintype "passive"))
      (node (ref "D22") (pin "2") (pinfunction "A_2") (pintype "passive"))
      (node (ref "IC2") (pin "6") (pinfunction "C10_6") (pintype "bidirectional"))
      (node (ref "R163") (pin "1") (pinfunction "1_1") (pintype "passive"))
    )
    (net (code "26") (name "/C10+") (class "Default")
      (node (ref "JP3") (pin "1") (pinfunction "1_1") (pintype "passive"))
      (node (ref "Q30") (pin "2") (pinfunction "S_2") (pintype "bidirectional"))
      (node (ref "R163") (pin "2") (pinfunction "2_2") (pintype "passive"))
      (node (ref "R168") (pin "1") (pinfunction "1_1") (pintype "passive"))
    )
    (net (code "27") (name "/C11") (class "Default")
      (node (ref "C45") (pin "1") (pinfunction "1_1") (pintype "passive"))
      (node (ref "C47") (pin "2") (pinfunction "2_2") (pintype "passive"))
      (node (ref "D22") (pin "1") (pinfunction "C_1") (pintype "passive"))
      (node (ref "D24") (pin "2") (pinfunction "A_2") (pintype "passive"))
      (node (ref "IC2") (pin "4") (pinfunction "C11_4") (pintype "bidirectional"))
      (node (ref "R171") (pin "1") (pinfunction "1_1") (pintype "passive"))
    )
    (net (code "28") (name "/C11+") (class "Default")
      (node (ref "JP3") (pin "2") (pinfunction "2_2") (pintype "passive"))
      (node (ref "Q32") (pin "2") (pinfunction "S_2") (pintype "bidirectional"))
      (node (ref "R171") (pin "2") (pinfunction "2_2") (pintype "passive"))
      (node (ref "R176") (pin "1") (pinfunction "1_1") (pintype "passive"))
    )
    (net (code "29") (name "/C12") (class "Default")
      (node (ref "C47") (pin "1") (pinfunction "1_1") (pintype "passive"))
      (node (ref "D24") (pin "1") (pinfunction "C_1") (pintype "passive"))
      (node (ref "IC2") (pin "2") (pinfunction "C12_2") (pintype "bidirectional"))
      (node (ref "R179") (pin "1") (pinfunction "1_1") (pintype "passive"))
    )
    (net (code "30") (name "/C12+") (class "Default")
      (node (ref "JP2") (pin "2") (pinfunction "2_2") (pintype "passive"))
      (node (ref "Q34") (pin "2") (pinfunction "S_2") (pintype "bidirectional"))
      (node (ref "R179") (pin "2") (pinfunction "2_2") (pintype "passive"))
      (node (ref "R9") (pin "2") (pinfunction "2_2") (pintype "passive"))
    )
    (net (code "31") (name "/C12+POWER") (class "Default")
      (node (ref "JP2") (pin "1") (pinfunction "1_1") (pintype "passive"))
      (node (ref "R15") (pin "2") (pinfunction "2_2") (pintype "passive"))
      (node (ref "R19") (pin "2") (pinfunction "2_2") (pintype "passive"))
    )
    (net (code "32") (name "/CSDSPL") (class "Default")
      (node (ref "CSLTC") (pin "2") (pinfunction "2_2") (pintype "passive"))
      (node (ref "JP1") (pin "6") (pinfunction "6_6") (pintype "passive"))
      (node (ref "U1") (pin "25") (pinfunction "IO19_25") (pintype "bidirectional"))
    )
    (net (code "33") (name "/CSLTC") (class "Default")
      (node (ref "CSLTC") (pin "1") (pinfunction "1_1") (pintype "passive"))
      (node (ref "IC2") (pin "41") (pinfunction "CSB_(IMA)_41") (pintype "bidirectional"))
      (node (ref "U1") (pin "24") (pinfunction "IO18_24") (pintype "bidirectional"))
    )
    (net (code "34") (name "/D+") (class "Default")
      (node (ref "D13") (pin "C") (pinfunction "C_C") (pintype "passive"))
      (node (ref "J1") (pin "A6") (pinfunction "DP1_A6") (pintype "bidirectional"))
      (node (ref "J1") (pin "B6") (pinfunction "DP2_B6") (pintype "bidirectional"))
      (node (ref "U1") (pin "18") (pinfunction "IO13_18") (pintype "bidirectional"))
    )
    (net (code "35") (name "/D-") (class "Default")
      (node (ref "D11") (pin "C") (pinfunction "C_C") (pintype "passive"))
      (node (ref "J1") (pin "A7") (pinfunction "DN1_A7") (pintype "bidirectional"))
      (node (ref "J1") (pin "B7") (pinfunction "DN2_B7") (pintype "bidirectional"))
      (node (ref "U1") (pin "17") (pinfunction "IO12_17") (pintype "bidirectional"))
    )
    (net (code "36") (name "/GND2") (class "Default")
      (node (ref "C1") (pin "2") (pinfunction "2_2") (pintype "passive"))
      (node (ref "C19") (pin "2") (pinfunction "2_2") (pintype "passive"))
      (node (ref "C2") (pin "-") (pinfunction "-_-") (pintype "passive"))
      (node (ref "C20") (pin "1") (pinfunction "1_1") (pintype "passive"))
      (node (ref "C23") (pin "2") (pinfunction "2_2") (pintype "passive"))
      (node (ref "C3") (pin "1") (pinfunction "1_1") (pintype "passive"))
      (node (ref "C4") (pin "2") (pinfunction "2_2") (pintype "passive"))
      (node (ref "D1") (pin "A") (pinfunction "A_A") (pintype "passive"))
      (node (ref "D7") (pin "C") (pinfunction "C_C") (pintype "passive"))
      (node (ref "IC2") (pin "30") (pinfunction "V-_1_30") (pintype "bidirectional"))
      (node (ref "IC2") (pin "31") (pinfunction "V-_2_31") (pintype "bidirectional"))
      (node (ref "IC2") (pin "40") (pinfunction "ISOMD_40") (pintype "bidirectional"))
      (node (ref "R17") (pin "1") (pinfunction "1_1") (pintype "passive"))
      (node (ref "R4") (pin "1") (pinfunction "1_1") (pintype "passive"))
      (node (ref "R57") (pin "1") (pinfunction "1_1") (pintype "passive"))
      (node (ref "R58") (pin "1") (pinfunction "1_1") (pintype "passive"))
      (node (ref "R59") (pin "2") (pinfunction "2_2") (pintype "passive"))
      (node (ref "R8") (pin "1") (pinfunction "1_1") (pintype "passive"))
    )
    (net (code "37") (name "/GPIO5") (class "Default")
      (node (ref "IC2") (pin "33") (pinfunction "GPIO5_33") (pintype "bidirectional"))
    )
    (net (code "38") (name "/IBIAS") (class "Default")
      (node (ref "IC2") (pin "45") (pinfunction "IBIAS_45") (pintype "bidirectional"))
      (node (ref "IC2") (pin "46") (pinfunction "ICMP_46") (pintype "bidirectional"))
      (node (ref "R17") (pin "2") (pinfunction "2_2") (pintype "passive"))
    )
    (net (code "39") (name "/IMB") (class "Default")
      (node (ref "IC2") (pin "47") (pinfunction "IMB_47") (pintype "bidirectional"))
      (node (ref "R1") (pin "1") (pinfunction "1_1") (pintype "passive"))
    )
    (net (code "40") (name "/IPB") (class "Default")
      (node (ref "IC2") (pin "48") (pinfunction "IPB_48") (pintype "bidirectional"))
      (node (ref "R1") (pin "2") (pinfunction "2_2") (pintype "passive"))
    )
    (net (code "41") (name "/LEDDATA") (class "Default")
      (node (ref "D15") (pin "1") (pinfunction "C_1") (pintype "passive"))
      (node (ref "U1") (pin "19") (pinfunction "IO14_19") (pintype "bidirectional"))
    )
    (net (code "42") (name "/MISO") (class "Default")
      (node (ref "IC2") (pin "44") (pinfunction "SDO_(NC)_44") (pintype "bidirectional"))
      (node (ref "MISO") (pin "1") (pinfunction "1_1") (pintype "passive"))
      (node (ref "R2") (pin "1") (pinfunction "1_1") (pintype "passive"))
      (node (ref "U1") (pin "16") (pinfunction "IO7_16") (pintype "bidirectional"))
    )
    (net (code "43") (name "/MODULEVOLTAGE") (class "Default")
      (node (ref "R15") (pin "1") (pinfunction "1_1") (pintype "passive"))
      (node (ref "R16") (pin "2") (pinfunction "2_2") (pintype "passive"))
      (node (ref "U1") (pin "6") (pinfunction "IO3_6") (pintype "bidirectional"))
    )
    (net (code "44") (name "/MOSI") (class "Default")
      (node (ref "IC2") (pin "43") (pinfunction "SDI_(NC)_43") (pintype "bidirectional"))
      (node (ref "JP1") (pin "3") (pinfunction "3_3") (pintype "passive"))
      (node (ref "U1") (pin "5") (pinfunction "IO2_5") (pintype "bidirectional"))
    )
    (net (code "45") (name "/RSTDSPL") (class "Default")
      (node (ref "JP1") (pin "5") (pinfunction "5_5") (pintype "passive"))
      (node (ref "U1") (pin "9") (pinfunction "IO4_9") (pintype "bidirectional"))
    )
    (net (code "46") (name "/S1") (class "Default")
      (node (ref "IC2") (pin "25") (pinfunction "S1_25") (pintype "bidirectional"))
      (node (ref "R97") (pin "1") (pinfunction "1_1") (pintype "passive"))
    )
    (net (code "47") (name "/S2") (class "Default")
      (node (ref "IC2") (pin "23") (pinfunction "S2_23") (pintype "bidirectional"))
      (node (ref "R102") (pin "1") (pinfunction "1_1") (pintype "passive"))
    )
    (net (code "48") (name "/S3") (class "Default")
      (node (ref "IC2") (pin "21") (pinfunction "S3_21") (pintype "bidirectional"))
      (node (ref "R106") (pin "1") (pinfunction "1_1") (pintype "passive"))
    )
    (net (code "49") (name "/S4") (class "Default")
      (node (ref "IC2") (pin "19") (pinfunction "S4_19") (pintype "bidirectional"))
      (node (ref "R114") (pin "1") (pinfunction "1_1") (pintype "passive"))
    )
    (net (code "50") (name "/S5") (class "Default")
      (node (ref "IC2") (pin "17") (pinfunction "S5_17") (pintype "bidirectional"))
      (node (ref "R122") (pin "1") (pinfunction "1_1") (pintype "passive"))
    )
    (net (code "51") (name "/S6") (class "Default")
      (node (ref "IC2") (pin "15") (pinfunction "S6_15") (pintype "bidirectional"))
      (node (ref "R130") (pin "1") (pinfunction "1_1") (pintype "passive"))
    )
    (net (code "52") (name "/S7") (class "Default")
      (node (ref "IC2") (pin "13") (pinfunction "S7_13") (pintype "bidirectional"))
      (node (ref "R138") (pin "1") (pinfunction "1_1") (pintype "passive"))
    )
    (net (code "53") (name "/S8") (class "Default")
      (node (ref "IC2") (pin "11") (pinfunction "S8_11") (pintype "bidirectional"))
      (node (ref "R146") (pin "1") (pinfunction "1_1") (pintype "passive"))
    )
    (net (code "54") (name "/S9") (class "Default")
      (node (ref "IC2") (pin "9") (pinfunction "S9_9") (pintype "bidirectional"))
      (node (ref "R154") (pin "1") (pinfunction "1_1") (pintype "passive"))
    )
    (net (code "55") (name "/S10") (class "Default")
      (node (ref "IC2") (pin "7") (pinfunction "S10_7") (pintype "bidirectional"))
      (node (ref "R162") (pin "1") (pinfunction "1_1") (pintype "passive"))
    )
    (net (code "56") (name "/S11") (class "Default")
      (node (ref "IC2") (pin "5") (pinfunction "S11_5") (pintype "bidirectional"))
      (node (ref "R170") (pin "1") (pinfunction "1_1") (pintype "passive"))
    )
    (net (code "57") (name "/S12") (class "Default")
      (node (ref "IC2") (pin "3") (pinfunction "S12_3") (pintype "bidirectional"))
      (node (ref "R178") (pin "1") (pinfunction "1_1") (pintype "passive"))
    )
    (net (code "58") (name "/SCLK") (class "Default")
      (node (ref "IC2") (pin "42") (pinfunction "SCK_(IPA)_42") (pintype "bidirectional"))
      (node (ref "JP1") (pin "2") (pinfunction "2_2") (pintype "passive"))
      (node (ref "U1") (pin "15") (pinfunction "IO6_15") (pintype "bidirectional"))
    )
    (net (code "59") (name "/V+") (class "Default")
      (node (ref "C20") (pin "2") (pinfunction "2_2") (pintype "passive"))
      (node (ref "IC2") (pin "1") (pinfunction "V+_1") (pintype "bidirectional"))
      (node (ref "R9") (pin "1") (pinfunction "1_1") (pintype "passive"))
    )
    (net (code "60") (name "/VREF1") (class "Default")
      (node (ref "C1") (pin "1") (pinfunction "1_1") (pintype "passive"))
      (node (ref "IC2") (pin "35") (pinfunction "VREF1_35") (pintype "bidirectional"))
    )
    (net (code "61") (name "/VREF2") (class "Default")
      (node (ref "C4") (pin "1") (pinfunction "1_1") (pintype "passive"))
      (node (ref "IC2") (pin "34") (pinfunction "VREF2_34") (pintype "bidirectional"))
      (node (ref "JP12") (pin "1") (pinfunction "1_1") (pintype "passive"))
      (node (ref "JP12") (pin "2") (pinfunction "2_2") (pintype "passive"))
      (node (ref "R3") (pin "2") (pinfunction "2_2") (pintype "passive"))
      (node (ref "R7") (pin "2") (pinfunction "2_2") (pintype "passive"))
    )
    (net (code "62") (name "/VTEMP1") (class "Default")
      (node (ref "IC2") (pin "27") (pinfunction "GPIO1_27") (pintype "bidirectional"))
      (node (ref "JP13") (pin "1") (pinfunction "1_1") (pintype "passive"))
      (node (ref "R57") (pin "2") (pinfunction "2_2") (pintype "passive"))
    )
    (net (code "63") (name "/VTEMP2") (class "Default")
      (node (ref "IC2") (pin "28") (pinfunction "GPIO2_28") (pintype "bidirectional"))
      (node (ref "JP13") (pin "2") (pinfunction "2_2") (pintype "passive"))
      (node (ref "R58") (pin "2") (pinfunction "2_2") (pintype "passive"))
    )
    (net (code "64") (name "/VTEMPNORTH") (class "Default")
      (node (ref "IC2") (pin "32") (pinfunction "GPIO4_32") (pintype "bidirectional"))
      (node (ref "R3") (pin "1") (pinfunction "1_1") (pintype "passive"))
      (node (ref "R4") (pin "2") (pinfunction "2_2") (pintype "passive"))
    )
    (net (code "65") (name "/VTEMPSOUTH") (class "Default")
      (node (ref "IC2") (pin "29") (pinfunction "GPIO3_29") (pintype "bidirectional"))
      (node (ref "R7") (pin "1") (pinfunction "1_1") (pintype "passive"))
      (node (ref "R8") (pin "2") (pinfunction "2_2") (pintype "passive"))
    )
    (net (code "66") (name "GND") (class "Default")
      (node (ref "BOOT") (pin "2") (pinfunction "2_2") (pintype "passive"))
      (node (ref "C10") (pin "2") (pinfunction "2_2") (pintype "passive"))
      (node (ref "C13") (pin "2") (pinfunction "2_2") (pintype "passive"))
      (node (ref "C14") (pin "2") (pinfunction "2_2") (pintype "passive"))
      (node (ref "C15") (pin "2") (pinfunction "2_2") (pintype "passive"))
      (node (ref "C16") (pin "1") (pinfunction "1_1") (pintype "passive"))
      (node (ref "C17") (pin "2") (pinfunction "2_2") (pintype "passive"))
      (node (ref "C21") (pin "2") (pinfunction "2_2") (pintype "passive"))
      (node (ref "C24") (pin "-") (pinfunction "-_-") (pintype "passive"))
      (node (ref "C26") (pin "-") (pinfunction "-_-") (pintype "passive"))
      (node (ref "C3") (pin "2") (pinfunction "2_2") (pintype "passive"))
      (node (ref "C5") (pin "2") (pinfunction "2_2") (pintype "passive"))
      (node (ref "C7") (pin "2") (pinfunction "2_2") (pintype "passive"))
      (node (ref "C8") (pin "2") (pinfunction "2_2") (pintype "passive"))
      (node (ref "C9") (pin "1") (pinfunction "1_1") (pintype "passive"))
      (node (ref "D1") (pin "C") (pinfunction "C_C") (pintype "passive"))
      (node (ref "D11") (pin "A") (pinfunction "A_A") (pintype "passive"))
      (node (ref "D13") (pin "A") (pinfunction "A_A") (pintype "passive"))
      (node (ref "D3") (pin "A") (pinfunction "A_A") (pintype "passive"))
      (node (ref "D7") (pin "A") (pinfunction "A_A") (pintype "passive"))
      (node (ref "D9") (pin "A") (pinfunction "A_A") (pintype "passive"))
      (node (ref "IC1") (pin "6") (pinfunction "EN_6") (pintype "bidirectional"))
      (node (ref "IC1") (pin "7") (pinfunction "GND_7") (pintype "bidirectional"))
      (node (ref "IC1") (pin "9") (pinfunction "EP_9") (pintype "bidirectional"))
      (node (ref "IC3") (pin "4") (pinfunction "GND1_4") (pintype "bidirectional"))
      (node (ref "IC4") (pin "1") (pinfunction "GND_1") (pintype "power_in"))
      (node (ref "J1") (pin "A1_B12") (pinfunction "GND_A1_B12") (pintype "power_in"))
      (node (ref "J1") (pin "B1_A12") (pinfunction "GND_B1_A12") (pintype "power_in"))
      (node (ref "J1") (pin "S1") (pinfunction "SHIELD_S1") (pintype "passive"))
      (node (ref "J1") (pin "S2") (pinfunction "SHIELD_S2") (pintype "passive"))
      (node (ref "J1") (pin "S3") (pinfunction "SHIELD_S3") (pintype "passive"))
      (node (ref "J1") (pin "S4") (pinfunction "SHIELD_S4") (pintype "passive"))
      (node (ref "JP1") (pin "7") (pinfunction "7_7") (pintype "passive"))
      (node (ref "JP10") (pin "1") (pinfunction "1_1") (pintype "passive"))
      (node (ref "LED2") (pin "VSS") (pinfunction "GND_VSS") (pintype "power_in"))
      (node (ref "R10") (pin "1") (pinfunction "1_1") (pintype "passive"))
      (node (ref "R11") (pin "1") (pinfunction "1_1") (pintype "passive"))
      (node (ref "R16") (pin "1") (pinfunction "1_1") (pintype "passive"))
      (node (ref "R55") (pin "1") (pinfunction "1_1") (pintype "passive"))
      (node (ref "RST") (pin "3") (pinfunction "P_3") (pintype "passive"))
      (node (ref "RST") (pin "4") (pinfunction "P1_4") (pintype "passive"))
      (node (ref "U1") (pin "1") (pinfunction "GND1_1") (pintype "power_in"))
      (node (ref "U1") (pin "11") (pinfunction "GND1_11") (pintype "power_in"))
      (node (ref "U1") (pin "14") (pinfunction "GND1_14") (pintype "power_in"))
      (node (ref "U1") (pin "2") (pinfunction "GND1_2") (pintype "power_in"))
      (node (ref "U1") (pin "36") (pinfunction "GND1_36") (pintype "power_in"))
      (node (ref "U1") (pin "37") (pinfunction "GND1_37") (pintype "power_in"))
      (node (ref "U1") (pin "38") (pinfunction "GND1_38") (pintype "power_in"))
      (node (ref "U1") (pin "39") (pinfunction "GND1_39") (pintype "power_in"))
      (node (ref "U1") (pin "40") (pinfunction "GND1_40") (pintype "power_in"))
      (node (ref "U1") (pin "41") (pinfunction "GND1_41") (pintype "power_in"))
      (node (ref "U1") (pin "42") (pinfunction "GND1_42") (pintype "power_in"))
      (node (ref "U1") (pin "43") (pinfunction "GND1_43") (pintype "power_in"))
      (node (ref "U1") (pin "44") (pinfunction "GND1_44") (pintype "power_in"))
      (node (ref "U1") (pin "45") (pinfunction "GND1_45") (pintype "power_in"))
      (node (ref "U1") (pin "46") (pinfunction "GND1_46") (pintype "power_in"))
      (node (ref "U1") (pin "47") (pinfunction "GND2_47") (pintype "power_in"))
      (node (ref "U1") (pin "48") (pinfunction "GND2_48") (pintype "power_in"))
      (node (ref "U1") (pin "49_1") (pinfunction "GND2_49_1") (pintype "power_in"))
      (node (ref "U1") (pin "49_2") (pinfunction "GND2_49_2") (pintype "power_in"))
      (node (ref "U1") (pin "49_3") (pinfunction "GND2_49_3") (pintype "power_in"))
      (node (ref "U1") (pin "49_4") (pinfunction "GND2_49_4") (pintype "power_in"))
      (node (ref "U1") (pin "49_5") (pinfunction "GND2_49_5") (pintype "power_in"))
      (node (ref "U1") (pin "49_6") (pinfunction "GND2_49_6") (pintype "power_in"))
      (node (ref "U1") (pin "49_7") (pinfunction "GND2_49_7") (pintype "power_in"))
      (node (ref "U1") (pin "49_8") (pinfunction "GND2_49_8") (pintype "power_in"))
      (node (ref "U1") (pin "49_9") (pinfunction "GND2_49_9") (pintype "power_in"))
      (node (ref "U1") (pin "50") (pinfunction "GND2_50") (pintype "power_in"))
      (node (ref "U1") (pin "51") (pinfunction "GND2_51") (pintype "power_in"))
      (node (ref "U1") (pin "52") (pinfunction "GND2_52") (pintype "power_in"))
      (node (ref "U1") (pin "53") (pinfunction "GND2_53") (pintype "power_in"))
    )
    (net (code "67") (name "Net-(D2-PadA)") (class "Default")
      (node (ref "D2") (pin "A") (pinfunction "A_A") (pintype "passive"))
      (node (ref "D9") (pin "C") (pinfunction "C_C") (pintype "passive"))
      (node (ref "J1") (pin "A4_B9") (pinfunction "VBUS_A4_B9") (pintype "power_in"))
      (node (ref "J1") (pin "B4_A9") (pinfunction "VBUS_B4_A9") (pintype "power_in"))
    )
    (net (code "68") (name "Net-(D15-A)") (class "Default")
      (node (ref "D15") (pin "2") (pinfunction "A_2") (pintype "passive"))
      (node (ref "LED2") (pin "DIN") (pinfunction "DI_DIN") (pintype "input"))
      (node (ref "R21") (pin "2") (pinfunction "2_2") (pintype "passive"))
    )
    (net (code "69") (name "Net-(IC1-CSP)") (class "Default")
      (node (ref "IC1") (pin "2") (pinfunction "CSP_2") (pintype "bidirectional"))
      (node (ref "L1") (pin "P$2") (pinfunction "2_P$2") (pintype "passive"))
      (node (ref "R5") (pin "1") (pinfunction "1_1") (pintype "passive"))
    )
    (net (code "70") (name "Net-(IC1-FB)") (class "Default")
      (node (ref "C6") (pin "2") (pinfunction "2_2") (pintype "passive"))
      (node (ref "IC1") (pin "8") (pinfunction "FB_8") (pintype "bidirectional"))
      (node (ref "R55") (pin "2") (pinfunction "2_2") (pintype "passive"))
      (node (ref "R6") (pin "1") (pinfunction "1_1") (pintype "passive"))
    )
    (net (code "71") (name "Net-(IC1-SW)") (class "Default")
      (node (ref "D3") (pin "C") (pinfunction "C_C") (pintype "passive"))
      (node (ref "IC1") (pin "5") (pinfunction "SW_5") (pintype "bidirectional"))
      (node (ref "L1") (pin "P$1") (pinfunction "1_P$1") (pintype "passive"))
    )
    (net (code "72") (name "Net-(IC1-VC)") (class "Default")
      (node (ref "C27") (pin "2") (pinfunction "2_2") (pintype "passive"))
      (node (ref "IC1") (pin "3") (pinfunction "VC_3") (pintype "bidirectional"))
    )
    (net (code "73") (name "Net-(IC1-VIN)") (class "Default")
      (node (ref "C21") (pin "1") (pinfunction "1_1") (pintype "passive"))
      (node (ref "C26") (pin "+") (pinfunction "+_+") (pintype "passive"))
      (node (ref "C27") (pin "1") (pinfunction "1_1") (pintype "passive"))
      (node (ref "IC1") (pin "4") (pinfunction "VIN_4") (pintype "bidirectional"))
      (node (ref "R19") (pin "1") (pinfunction "1_1") (pintype "passive"))
    )
    (net (code "74") (name "Net-(IC3-CANH)") (class "Default")
      (node (ref "IC3") (pin "7") (pinfunction "CANH_7") (pintype "bidirectional"))
      (node (ref "JP7") (pin "2") (pinfunction "2_2") (pintype "bidirectional"))
      (node (ref "TERM") (pin "1") (pinfunction "1_1") (pintype "passive"))
    )
    (net (code "75") (name "Net-(IC3-CANL)") (class "Default")
      (node (ref "IC3") (pin "6") (pinfunction "CANL_6") (pintype "bidirectional"))
      (node (ref "JP7") (pin "3") (pinfunction "3_3") (pintype "bidirectional"))
      (node (ref "R12") (pin "1") (pinfunction "1_1") (pintype "passive"))
    )
    (net (code "76") (name "Net-(IC3-GND2)") (class "Default")
      (node (ref "C11") (pin "2") (pinfunction "2_2") (pintype "passive"))
      (node (ref "C12") (pin "2") (pinfunction "2_2") (pintype "passive"))
      (node (ref "IC3") (pin "5") (pinfunction "GND2_5") (pintype "bidirectional"))
      (node (ref "JP7") (pin "4") (pinfunction "4_4") (pintype "bidirectional"))
    )
    (net (code "77") (name "Net-(IC3-RXD)") (class "Default")
      (node (ref "IC3") (pin "3") (pinfunction "RXD_3") (pintype "bidirectional"))
      (node (ref "U1") (pin "29") (pinfunction "IO23_29") (pintype "bidirectional"))
    )
    (net (code "78") (name "Net-(IC3-TXD)") (class "Default")
      (node (ref "IC3") (pin "2") (pinfunction "TXD_2") (pintype "bidirectional"))
      (node (ref "U1") (pin "28") (pinfunction "IO22_28") (pintype "bidirectional"))
    )
    (net (code "79") (name "Net-(IC3-VCC2)") (class "Default")
      (node (ref "C11") (pin "1") (pinfunction "1_1") (pintype "passive"))
      (node (ref "C12") (pin "1") (pinfunction "1_1") (pintype "passive"))
      (node (ref "IC3") (pin "8") (pinfunction "VCC2_8") (pintype "bidirectional"))
      (node (ref "JP7") (pin "1") (pinfunction "1_1") (pintype "bidirectional"))
    )
    (net (code "80") (name "Net-(J1-CC1)") (class "Default")
      (node (ref "J1") (pin "A5") (pinfunction "CC1_A5") (pintype "bidirectional"))
      (node (ref "R10") (pin "2") (pinfunction "2_2") (pintype "passive"))
    )
    (net (code "81") (name "Net-(J1-CC2)") (class "Default")
      (node (ref "J1") (pin "B5") (pinfunction "CC2_B5") (pintype "bidirectional"))
      (node (ref "R11") (pin "2") (pinfunction "2_2") (pintype "passive"))
    )
    (net (code "82") (name "Net-(Q14-D)") (class "Default")
      (node (ref "Q14") (pin "3") (pinfunction "D_3") (pintype "bidirectional"))
      (node (ref "R96") (pin "2") (pinfunction "2_2") (pintype "passive"))
    )
    (net (code "83") (name "Net-(Q14-G)") (class "Default")
      (node (ref "Q14") (pin "1") (pinfunction "G_1") (pintype "bidirectional"))
      (node (ref "R97") (pin "2") (pinfunction "2_2") (pintype "passive"))
    )
    (net (code "84") (name "Net-(Q15-D)") (class "Default")
      (node (ref "Q15") (pin "3") (pinfunction "D_3") (pintype "bidirectional"))
      (node (ref "R101") (pin "2") (pinfunction "2_2") (pintype "passive"))
    )
    (net (code "85") (name "Net-(Q15-G)") (class "Default")
      (node (ref "Q15") (pin "1") (pinfunction "G_1") (pintype "bidirectional"))
      (node (ref "R102") (pin "2") (pinfunction "2_2") (pintype "passive"))
    )
    (net (code "86") (name "Net-(Q16-D)") (class "Default")
      (node (ref "Q16") (pin "3") (pinfunction "D_3") (pintype "bidirectional"))
      (node (ref "R105") (pin "2") (pinfunction "2_2") (pintype "passive"))
    )
    (net (code "87") (name "Net-(Q16-G)") (class "Default")
      (node (ref "Q16") (pin "1") (pinfunction "G_1") (pintype "bidirectional"))
      (node (ref "R106") (pin "2") (pinfunction "2_2") (pintype "passive"))
    )
    (net (code "88") (name "Net-(Q18-D)") (class "Default")
      (node (ref "Q18") (pin "3") (pinfunction "D_3") (pintype "bidirectional"))
      (node (ref "R113") (pin "2") (pinfunction "2_2") (pintype "passive"))
    )
    (net (code "89") (name "Net-(Q18-G)") (class "Default")
      (node (ref "Q18") (pin "1") (pinfunction "G_1") (pintype "bidirectional"))
      (node (ref "R114") (pin "2") (pinfunction "2_2") (pintype "passive"))
    )
    (net (code "90") (name "Net-(Q20-D)") (class "Default")
      (node (ref "Q20") (pin "3") (pinfunction "D_3") (pintype "bidirectional"))
      (node (ref "R121") (pin "2") (pinfunction "2_2") (pintype "passive"))
    )
    (net (code "91") (name "Net-(Q20-G)") (class "Default")
      (node (ref "Q20") (pin "1") (pinfunction "G_1") (pintype "bidirectional"))
      (node (ref "R122") (pin "2") (pinfunction "2_2") (pintype "passive"))
    )
    (net (code "92") (name "Net-(Q22-D)") (class "Default")
      (node (ref "Q22") (pin "3") (pinfunction "D_3") (pintype "bidirectional"))
      (node (ref "R129") (pin "2") (pinfunction "2_2") (pintype "passive"))
    )
    (net (code "93") (name "Net-(Q22-G)") (class "Default")
      (node (ref "Q22") (pin "1") (pinfunction "G_1") (pintype "bidirectional"))
      (node (ref "R130") (pin "2") (pinfunction "2_2") (pintype "passive"))
    )
    (net (code "94") (name "Net-(Q24-D)") (class "Default")
      (node (ref "Q24") (pin "3") (pinfunction "D_3") (pintype "bidirectional"))
      (node (ref "R137") (pin "2") (pinfunction "2_2") (pintype "passive"))
    )
    (net (code "95") (name "Net-(Q24-G)") (class "Default")
      (node (ref "Q24") (pin "1") (pinfunction "G_1") (pintype "bidirectional"))
      (node (ref "R138") (pin "2") (pinfunction "2_2") (pintype "passive"))
    )
    (net (code "96") (name "Net-(Q26-D)") (class "Default")
      (node (ref "Q26") (pin "3") (pinfunction "D_3") (pintype "bidirectional"))
      (node (ref "R145") (pin "2") (pinfunction "2_2") (pintype "passive"))
    )
    (net (code "97") (name "Net-(Q26-G)") (class "Default")
      (node (ref "Q26") (pin "1") (pinfunction "G_1") (pintype "bidirectional"))
      (node (ref "R146") (pin "2") (pinfunction "2_2") (pintype "passive"))
    )
    (net (code "98") (name "Net-(Q28-D)") (class "Default")
      (node (ref "Q28") (pin "3") (pinfunction "D_3") (pintype "bidirectional"))
      (node (ref "R153") (pin "2") (pinfunction "2_2") (pintype "passive"))
    )
    (net (code "99") (name "Net-(Q28-G)") (class "Default")
      (node (ref "Q28") (pin "1") (pinfunction "G_1") (pintype "bidirectional"))
      (node (ref "R154") (pin "2") (pinfunction "2_2") (pintype "passive"))
    )
    (net (code "100") (name "Net-(Q30-D)") (class "Default")
      (node (ref "Q30") (pin "3") (pinfunction "D_3") (pintype "bidirectional"))
      (node (ref "R161") (pin "2") (pinfunction "2_2") (pintype "passive"))
    )
    (net (code "101") (name "Net-(Q30-G)") (class "Default")
      (node (ref "Q30") (pin "1") (pinfunction "G_1") (pintype "bidirectional"))
      (node (ref "R162") (pin "2") (pinfunction "2_2") (pintype "passive"))
    )
    (net (code "102") (name "Net-(Q32-D)") (class "Default")
      (node (ref "Q32") (pin "3") (pinfunction "D_3") (pintype "bidirectional"))
      (node (ref "R169") (pin "2") (pinfunction "2_2") (pintype "passive"))
    )
    (net (code "103") (name "Net-(Q32-G)") (class "Default")
      (node (ref "Q32") (pin "1") (pinfunction "G_1") (pintype "bidirectional"))
      (node (ref "R170") (pin "2") (pinfunction "2_2") (pintype "passive"))
    )
    (net (code "104") (name "Net-(Q34-D)") (class "Default")
      (node (ref "Q34") (pin "3") (pinfunction "D_3") (pintype "bidirectional"))
      (node (ref "R177") (pin "2") (pinfunction "2_2") (pintype "passive"))
    )
    (net (code "105") (name "Net-(Q34-G)") (class "Default")
      (node (ref "Q34") (pin "1") (pinfunction "G_1") (pintype "bidirectional"))
      (node (ref "R178") (pin "2") (pinfunction "2_2") (pintype "passive"))
    )
    (net (code "106") (name "Net-(R12-Pad2)") (class "Default")
      (node (ref "R12") (pin "2") (pinfunction "2_2") (pintype "passive"))
      (node (ref "TERM") (pin "2") (pinfunction "2_2") (pintype "passive"))
    )
    (net (code "107") (name "Net-(R82-Pad2)") (class "Default")
      (node (ref "R82") (pin "2") (pinfunction "2_2") (pintype "passive"))
      (node (ref "R96") (pin "1") (pinfunction "1_1") (pintype "passive"))
    )
    (net (code "108") (name "Net-(R100-Pad2)") (class "Default")
      (node (ref "R100") (pin "2") (pinfunction "2_2") (pintype "passive"))
      (node (ref "R101") (pin "1") (pinfunction "1_1") (pintype "passive"))
    )
    (net (code "109") (name "Net-(R104-Pad2)") (class "Default")
      (node (ref "R104") (pin "2") (pinfunction "2_2") (pintype "passive"))
      (node (ref "R105") (pin "1") (pinfunction "1_1") (pintype "passive"))
    )
    (net (code "110") (name "Net-(R112-Pad2)") (class "Default")
      (node (ref "R112") (pin "2") (pinfunction "2_2") (pintype "passive"))
      (node (ref "R113") (pin "1") (pinfunction "1_1") (pintype "passive"))
    )
    (net (code "111") (name "Net-(R120-Pad2)") (class "Default")
      (node (ref "R120") (pin "2") (pinfunction "2_2") (pintype "passive"))
      (node (ref "R121") (pin "1") (pinfunction "1_1") (pintype "passive"))
    )
    (net (code "112") (name "Net-(R128-Pad2)") (class "Default")
      (node (ref "R128") (pin "2") (pinfunction "2_2") (pintype "passive"))
      (node (ref "R129") (pin "1") (pinfunction "1_1") (pintype "passive"))
    )
    (net (code "113") (name "Net-(R136-Pad2)") (class "Default")
      (node (ref "R136") (pin "2") (pinfunction "2_2") (pintype "passive"))
      (node (ref "R137") (pin "1") (pinfunction "1_1") (pintype "passive"))
    )
    (net (code "114") (name "Net-(R144-Pad2)") (class "Default")
      (node (ref "R144") (pin "2") (pinfunction "2_2") (pintype "passive"))
      (node (ref "R145") (pin "1") (pinfunction "1_1") (pintype "passive"))
    )
    (net (code "115") (name "Net-(R152-Pad2)") (class "Default")
      (node (ref "R152") (pin "2") (pinfunction "2_2") (pintype "passive"))
      (node (ref "R153") (pin "1") (pinfunction "1_1") (pintype "passive"))
    )
    (net (code "116") (name "Net-(R160-Pad2)") (class "Default")
      (node (ref "R160") (pin "2") (pinfunction "2_2") (pintype "passive"))
      (node (ref "R161") (pin "1") (pinfunction "1_1") (pintype "passive"))
    )
    (net (code "117") (name "Net-(R168-Pad2)") (class "Default")
      (node (ref "R168") (pin "2") (pinfunction "2_2") (pintype "passive"))
      (node (ref "R169") (pin "1") (pinfunction "1_1") (pintype "passive"))
    )
    (net (code "118") (name "Net-(R176-Pad2)") (class "Default")
      (node (ref "R176") (pin "2") (pinfunction "2_2") (pintype "passive"))
      (node (ref "R177") (pin "1") (pinfunction "1_1") (pintype "passive"))
    )
    (net (code "119") (name "Net-(RST-S)") (class "Default")
      (node (ref "C13") (pin "1") (pinfunction "1_1") (pintype "passive"))
      (node (ref "R13") (pin "1") (pinfunction "1_1") (pintype "passive"))
      (node (ref "RST") (pin "1") (pinfunction "S_1") (pintype "passive"))
      (node (ref "RST") (pin "2") (pinfunction "S1_2") (pintype "passive"))
      (node (ref "U1") (pin "8") (pinfunction "EN_8") (pintype "input"))
    )
    (net (code "120") (name "Net-(U1-IO0)") (class "Default")
      (node (ref "C9") (pin "2") (pinfunction "2_2") (pintype "passive"))
      (node (ref "R20") (pin "1") (pinfunction "1_1") (pintype "passive"))
      (node (ref "U1") (pin "12") (pinfunction "IO0_12") (pintype "bidirectional"))
      (node (ref "Y1") (pin "2") (pinfunction "2_2") (pintype "bidirectional"))
    )
    (net (code "121") (name "Net-(U1-IO1)") (class "Default")
      (node (ref "C16") (pin "2") (pinfunction "2_2") (pintype "passive"))
      (node (ref "R20") (pin "2") (pinfunction "2_2") (pintype "passive"))
      (node (ref "U1") (pin "13") (pinfunction "IO1_13") (pintype "bidirectional"))
      (node (ref "Y1") (pin "1") (pinfunction "1_1") (pintype "bidirectional"))
    )
    (net (code "122") (name "Net-(U1-IO8)") (class "Default")
      (node (ref "R14") (pin "1") (pinfunction "1_1") (pintype "passive"))
      (node (ref "U1") (pin "22") (pinfunction "IO8_22") (pintype "bidirectional"))
    )
    (net (code "123") (name "Net-(U1-IO9)") (class "Default")
      (node (ref "BOOT") (pin "1") (pinfunction "1_1") (pintype "passive"))
      (node (ref "U1") (pin "23") (pinfunction "IO9_23") (pintype "bidirectional"))
    )
    (net (code "124") (name "Net-(U1-RXD0)") (class "Default")
      (node (ref "RX") (pin "TP") (pinfunction "TP_TP") (pintype "input"))
      (node (ref "U1") (pin "30") (pinfunction "RXD0_30") (pintype "bidirectional"))
    )
    (net (code "125") (name "Net-(U1-TXD0)") (class "Default")
      (node (ref "TX") (pin "TP") (pinfunction "TP_TP") (pintype "input"))
      (node (ref "U1") (pin "31") (pinfunction "TXD0_31") (pintype "bidirectional"))
    )
    (net (code "126") (name "unconnected-(IC2-DRIVE-Pad38)") (class "Default")
      (node (ref "IC2") (pin "38") (pinfunction "DRIVE_38") (pintype "bidirectional"))
    )
    (net (code "127") (name "unconnected-(IC2-WDT-Pad39)") (class "Default")
      (node (ref "IC2") (pin "39") (pinfunction "WDT_39") (pintype "bidirectional"))
    )
    (net (code "128") (name "unconnected-(J1-SBU1-PadA8)") (class "Default")
      (node (ref "J1") (pin "A8") (pinfunction "SBU1_A8") (pintype "bidirectional"))
    )
    (net (code "129") (name "unconnected-(J1-SBU2-PadB8)") (class "Default")
      (node (ref "J1") (pin "B8") (pinfunction "SBU2_B8") (pintype "bidirectional"))
    )
    (net (code "130") (name "unconnected-(JP6-Pad1)") (class "Default")
      (node (ref "JP6") (pin "1") (pinfunction "1_1") (pintype "passive"))
    )
    (net (code "131") (name "unconnected-(JP8-Pad2)") (class "Default")
      (node (ref "JP8") (pin "2") (pinfunction "2_2") (pintype "passive"))
    )
    (net (code "132") (name "unconnected-(JP11-Pad2)") (class "Default")
      (node (ref "JP11") (pin "2") (pinfunction "2_2") (pintype "passive"))
    )
    (net (code "133") (name "unconnected-(LED2-DO-PadDOUT)") (class "Default")
      (node (ref "LED2") (pin "DOUT") (pinfunction "DO_DOUT") (pintype "output"))
    )
    (net (code "134") (name "unconnected-(U1-IO15-Pad20)") (class "Default")
      (node (ref "U1") (pin "20") (pinfunction "IO15_20") (pintype "bidirectional"))
    )
    (net (code "135") (name "unconnected-(U1-IO20-Pad26)") (class "Default")
      (node (ref "U1") (pin "26") (pinfunction "IO20_26") (pintype "bidirectional"))
    )
    (net (code "136") (name "unconnected-(U1-IO21-Pad27)") (class "Default")
      (node (ref "U1") (pin "27") (pinfunction "IO21_27") (pintype "bidirectional"))
    )
    (net (code "137") (name "unconnected-(U1-NC-Pad4)") (class "Default")
      (node (ref "U1") (pin "4") (pinfunction "NC_4") (pintype "no_connect"))
    )
    (net (code "138") (name "unconnected-(U1-NC-Pad7)") (class "Default")
      (node (ref "U1") (pin "7") (pinfunction "NC_7") (pintype "no_connect"))
    )
    (net (code "139") (name "unconnected-(U1-NC-Pad21)") (class "Default")
      (node (ref "U1") (pin "21") (pinfunction "NC_21") (pintype "no_connect"))
    )
    (net (code "140") (name "unconnected-(U1-NC-Pad32)") (class "Default")
      (node (ref "U1") (pin "32") (pinfunction "NC_32") (pintype "no_connect"))
    )
    (net (code "141") (name "unconnected-(U1-NC-Pad33)") (class "Default")
      (node (ref "U1") (pin "33") (pinfunction "NC_33") (pintype "no_connect"))
    )
    (net (code "142") (name "unconnected-(U1-NC-Pad34)") (class "Default")
      (node (ref "U1") (pin "34") (pinfunction "NC_34") (pintype "no_connect"))
    )
    (net (code "143") (name "unconnected-(U1-NC-Pad35)") (class "Default")
      (node (ref "U1") (pin "35") (pinfunction "NC_35") (pintype "no_connect"))
    )
  )
)
